# shelves_v05.net
KiCad netlist of a schematic drawn in EAGLE
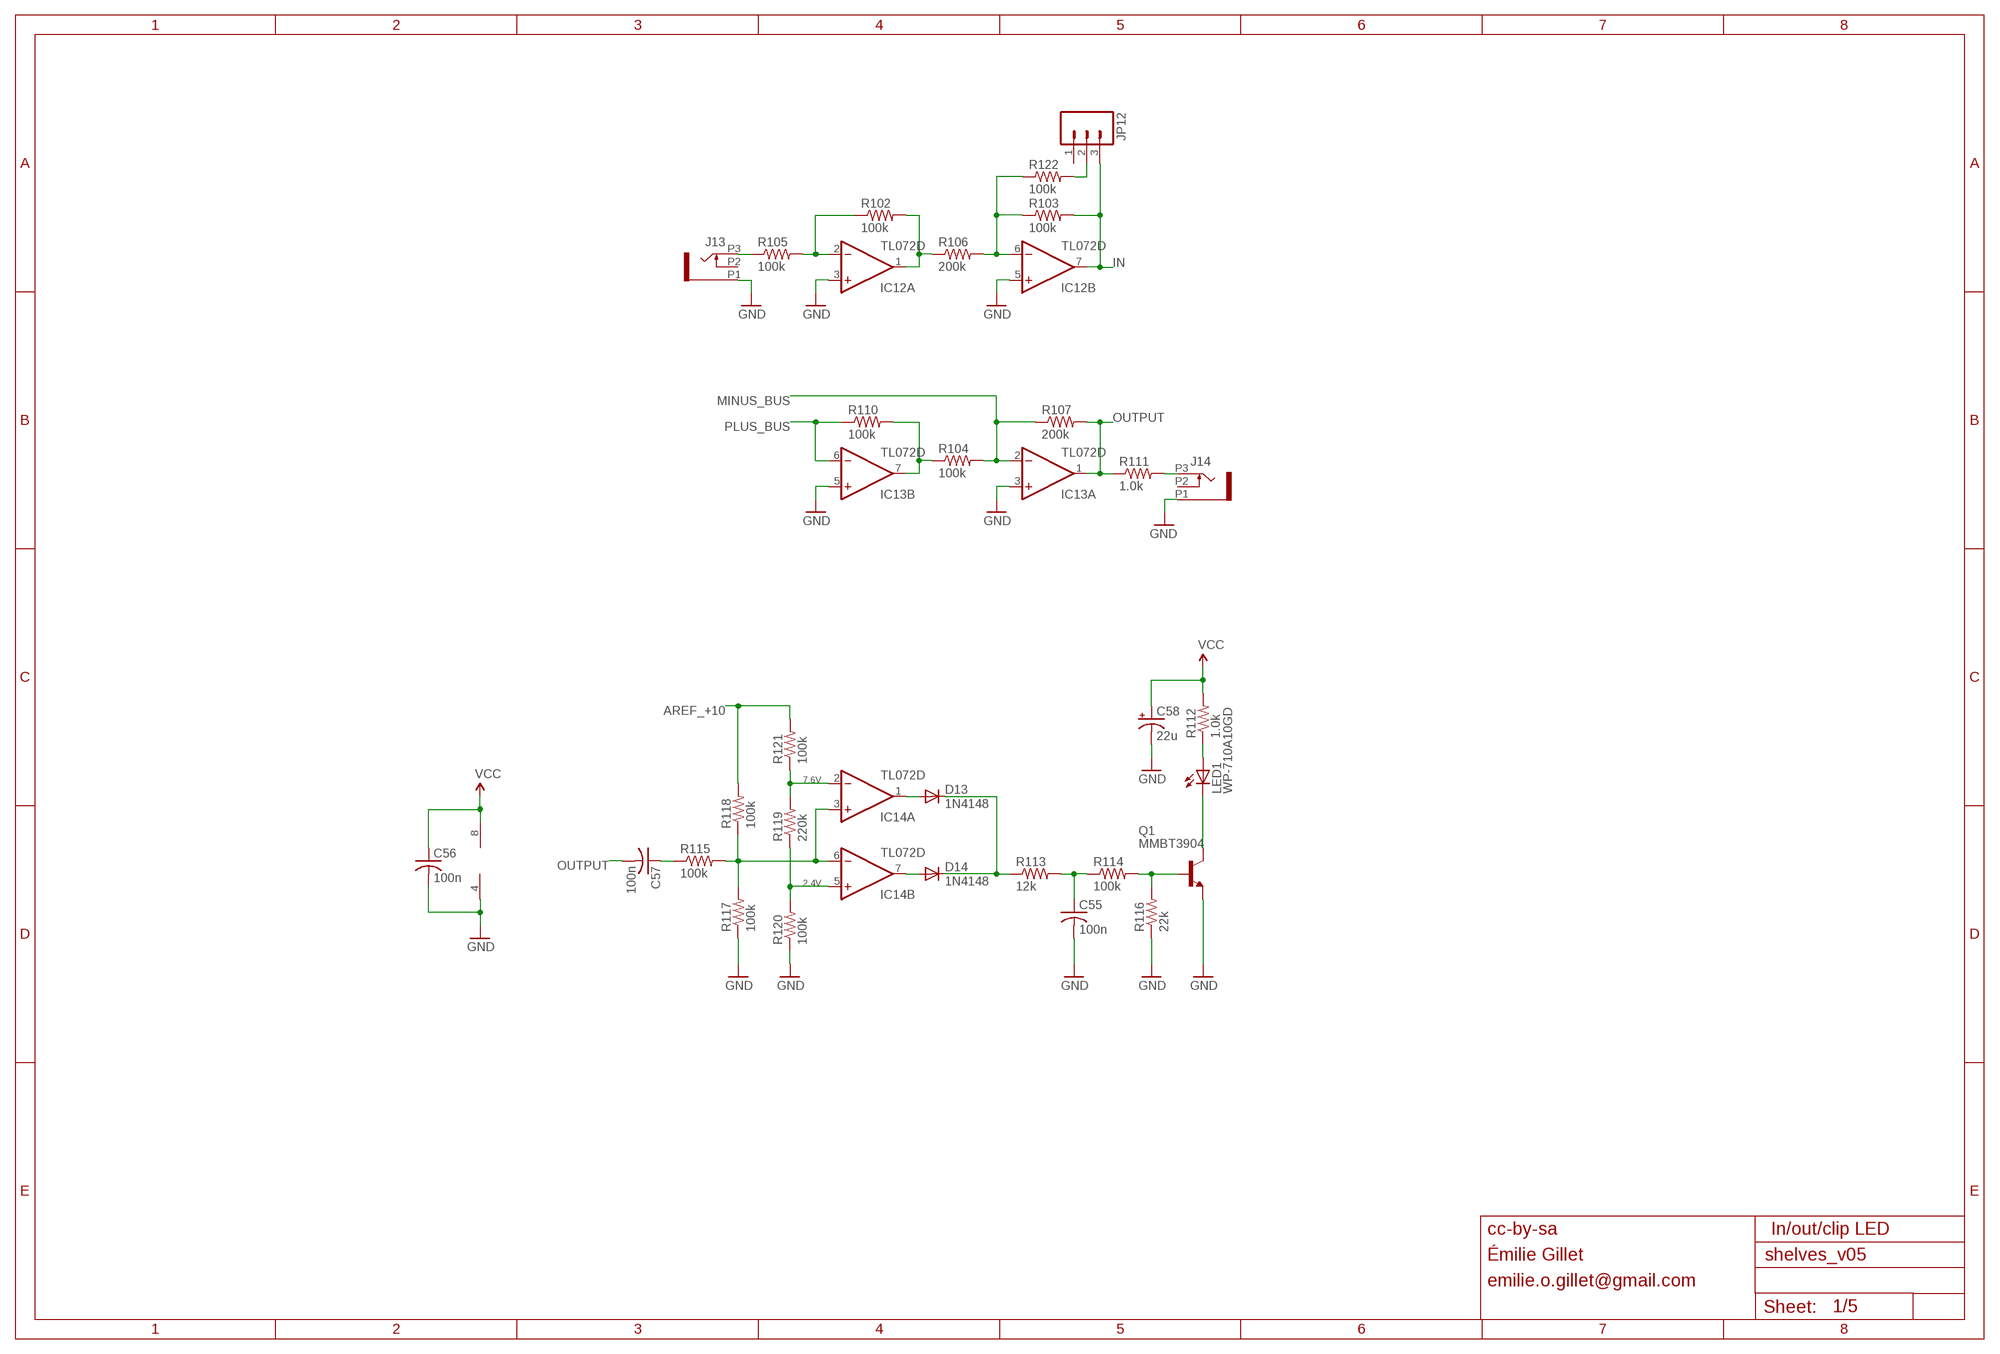
[diagram p0: schematic, sheet 1]
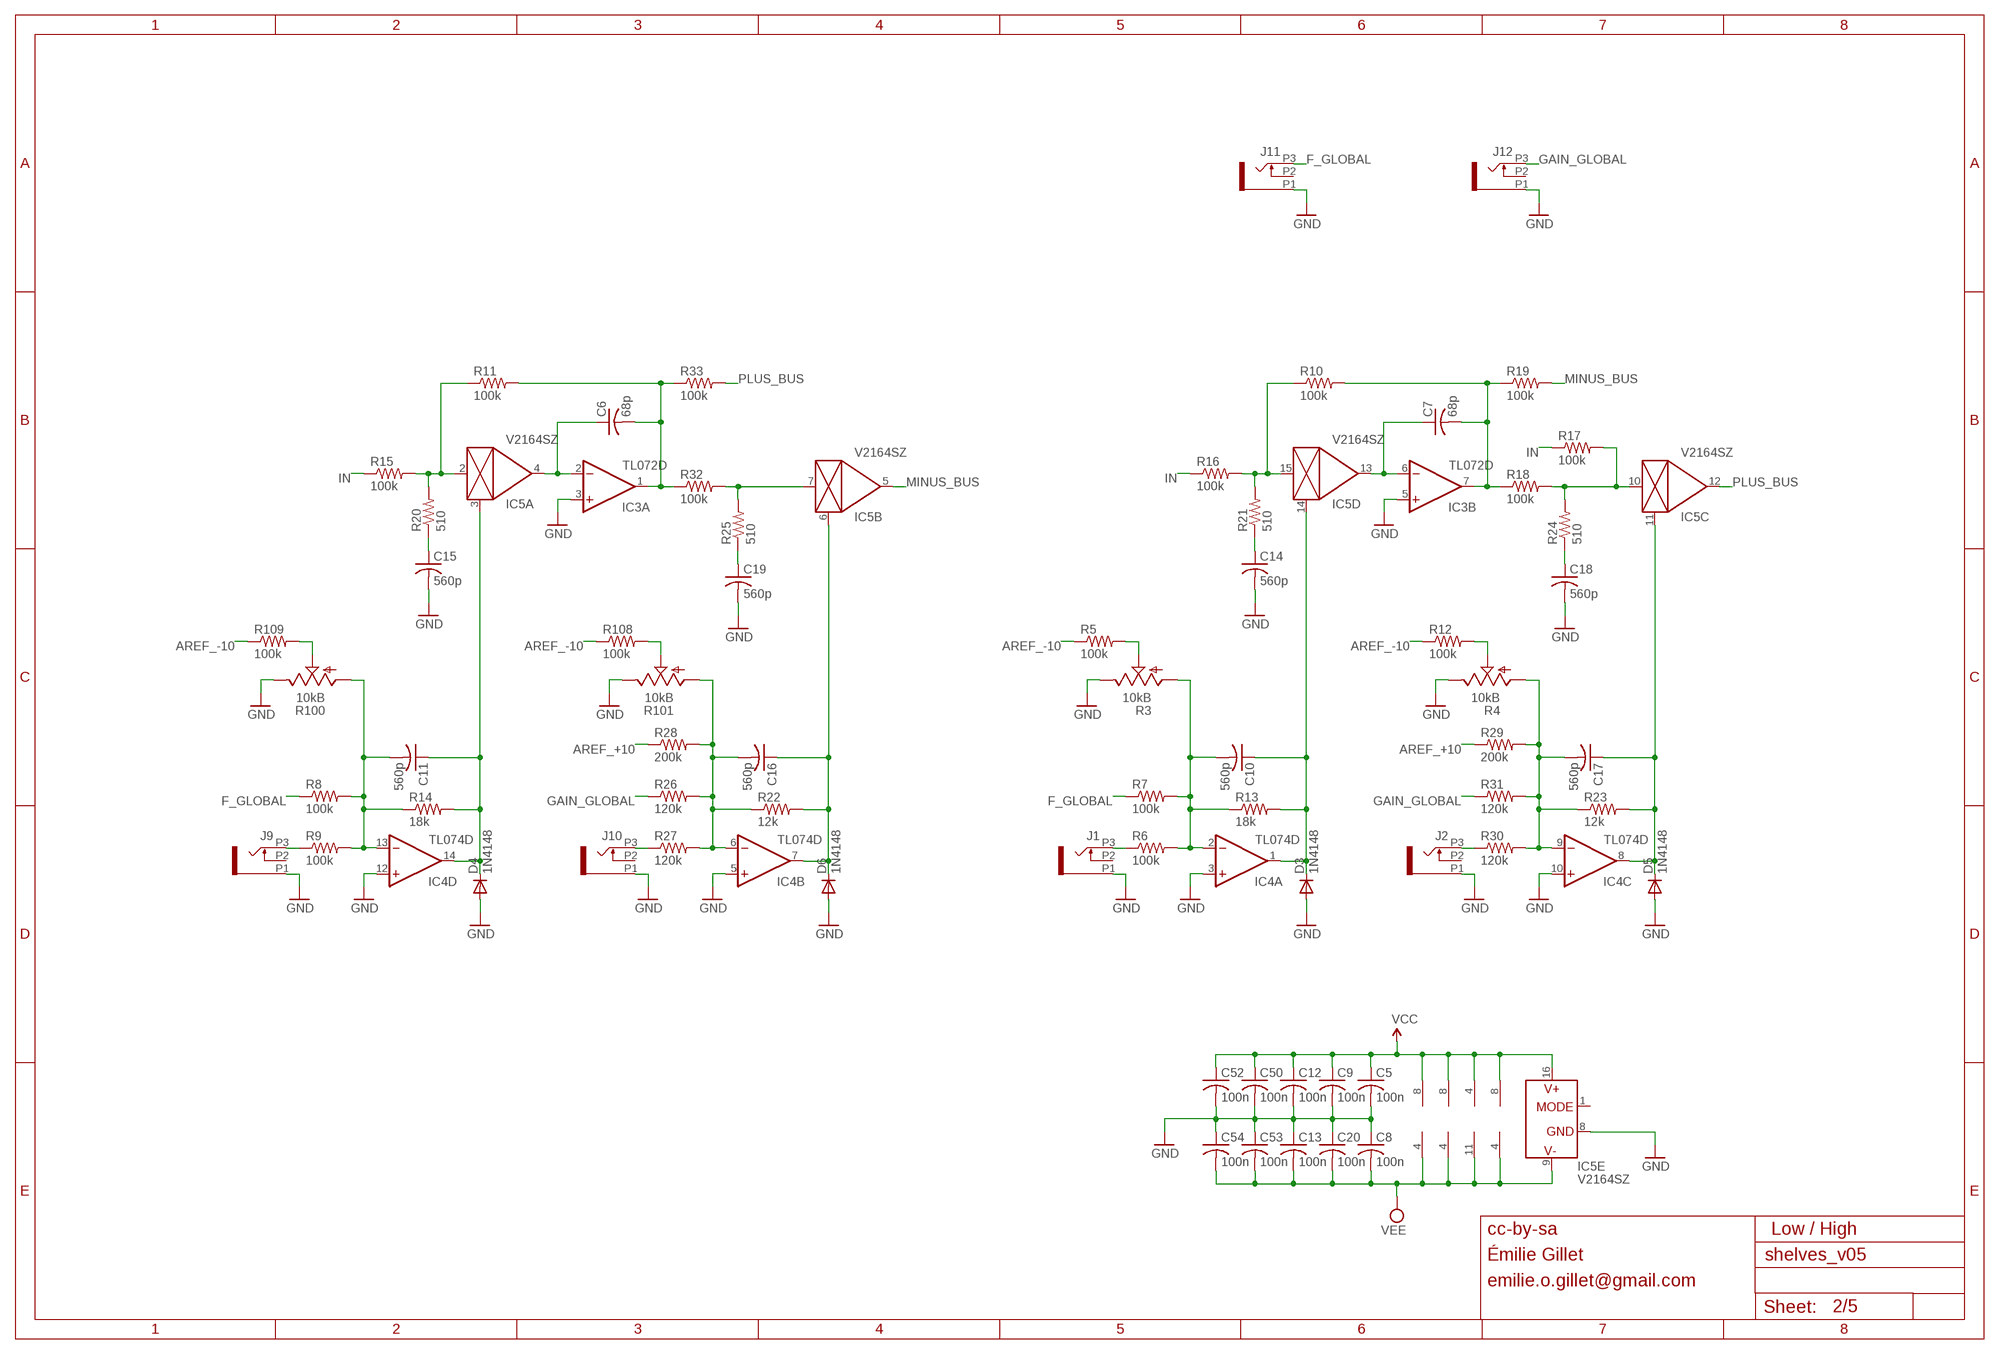
[diagram p1: schematic, sheet 2]
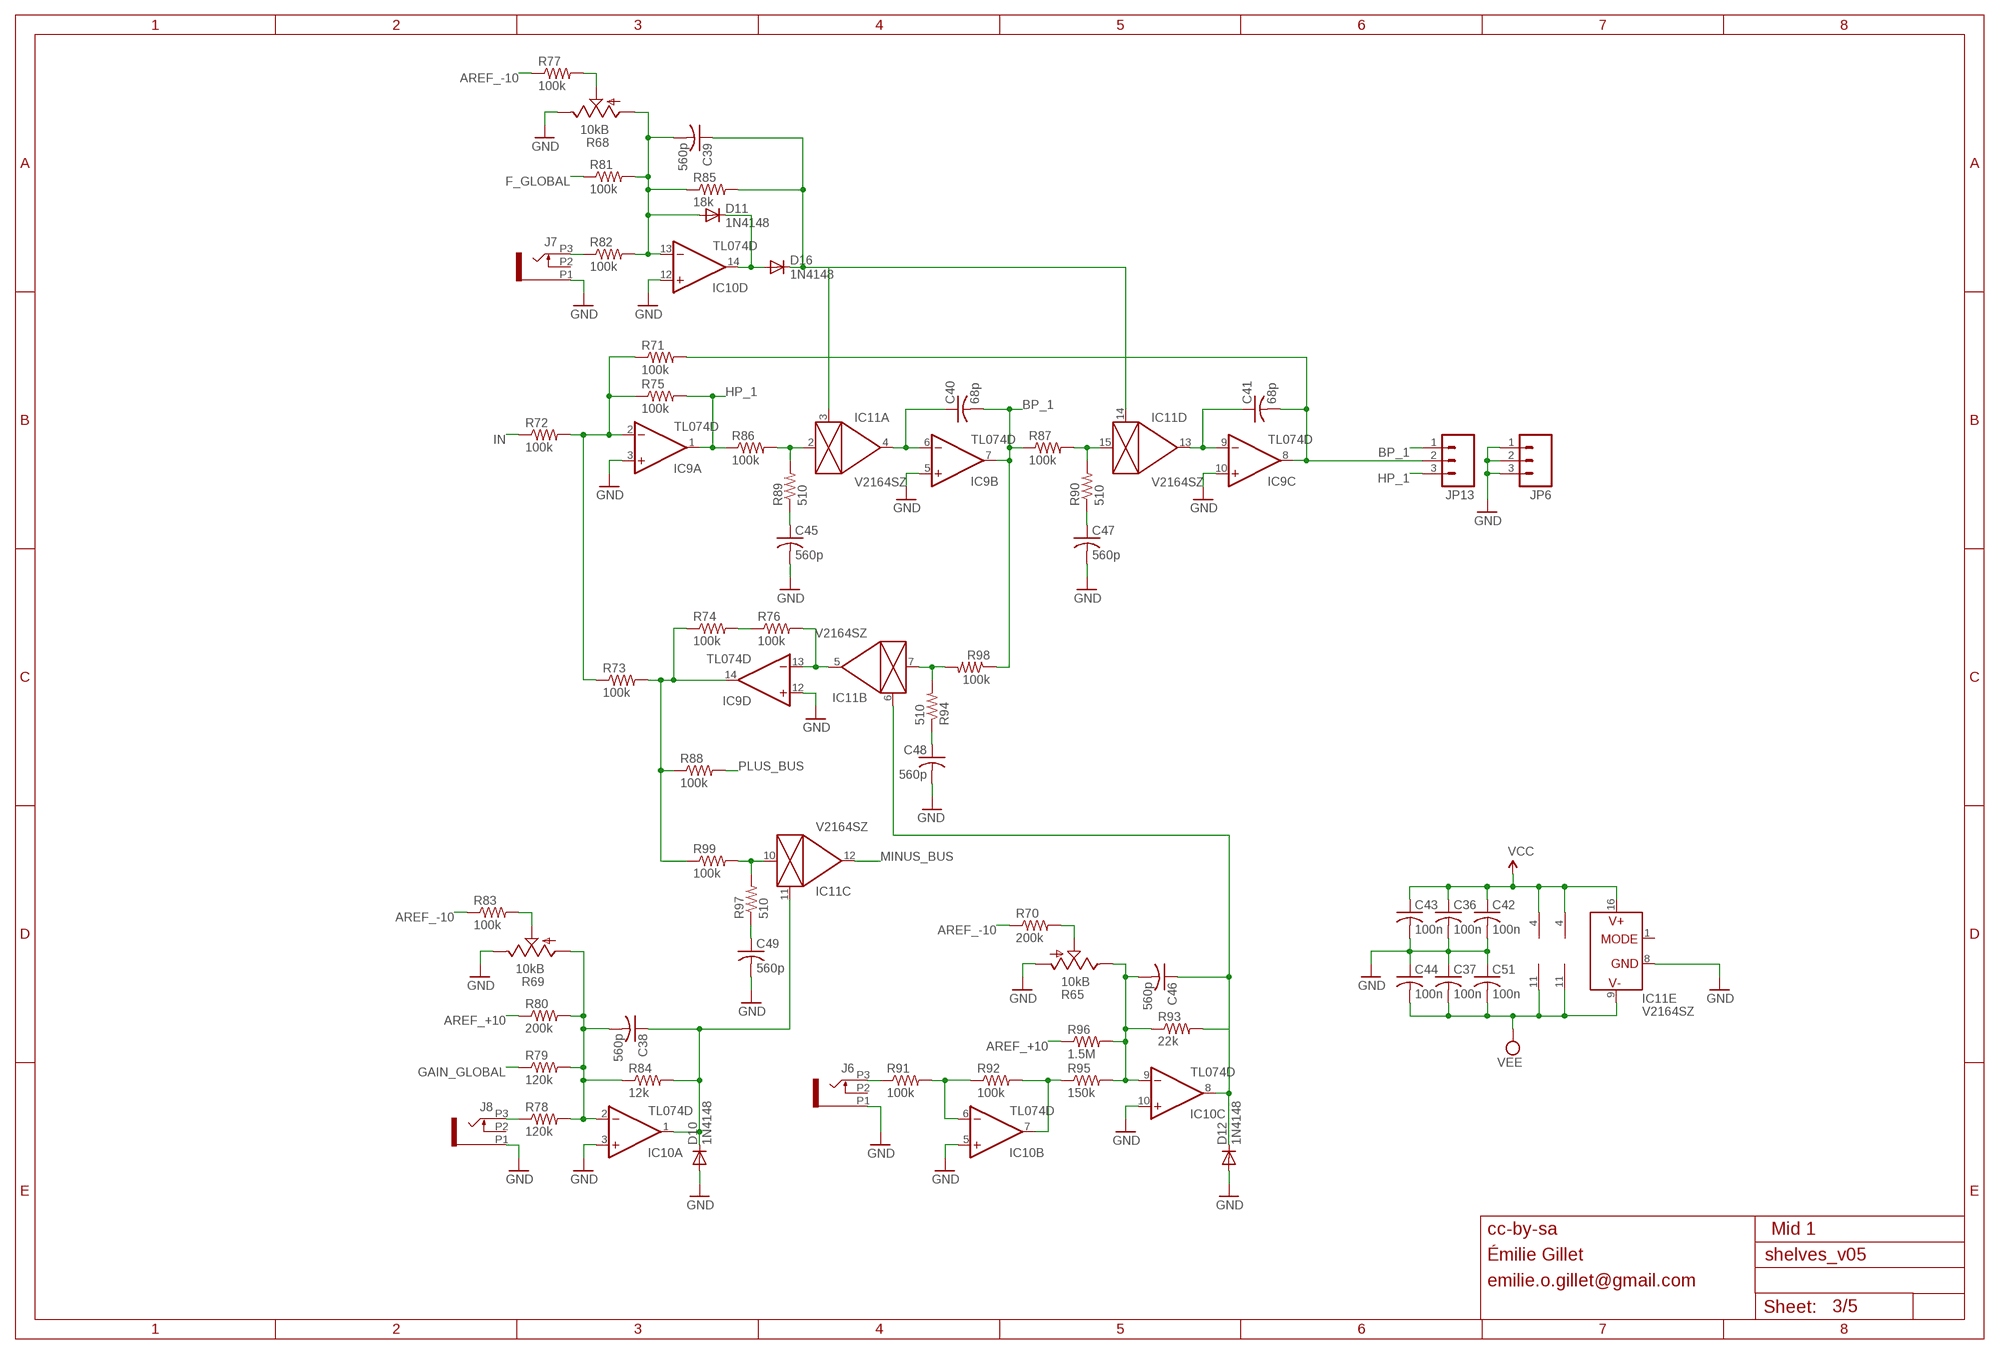
[diagram p2: schematic, sheet 3]
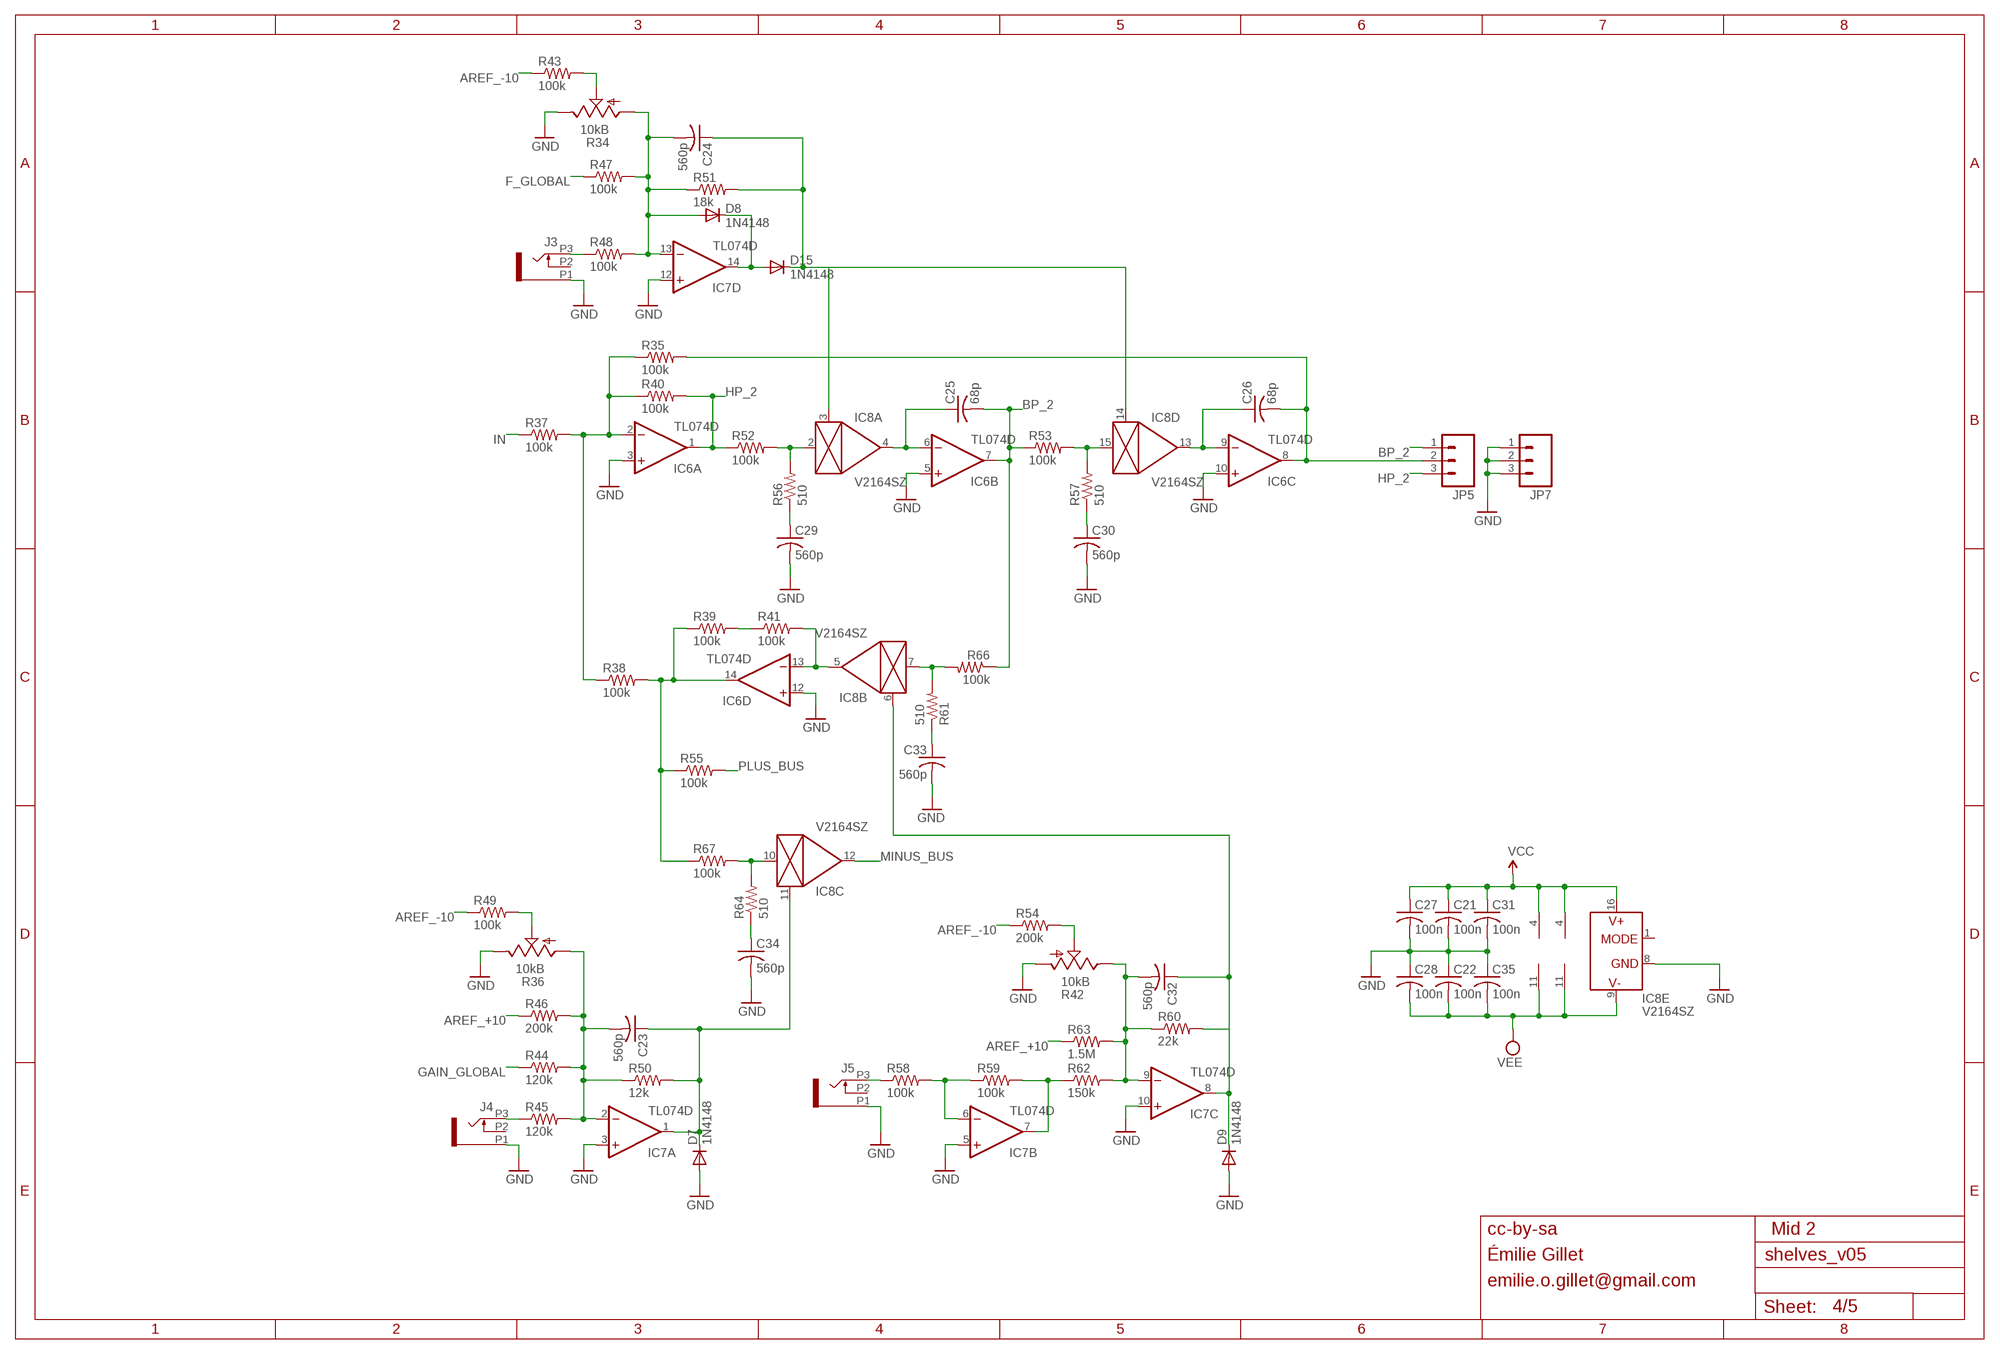
[diagram p3: schematic, sheet 4]
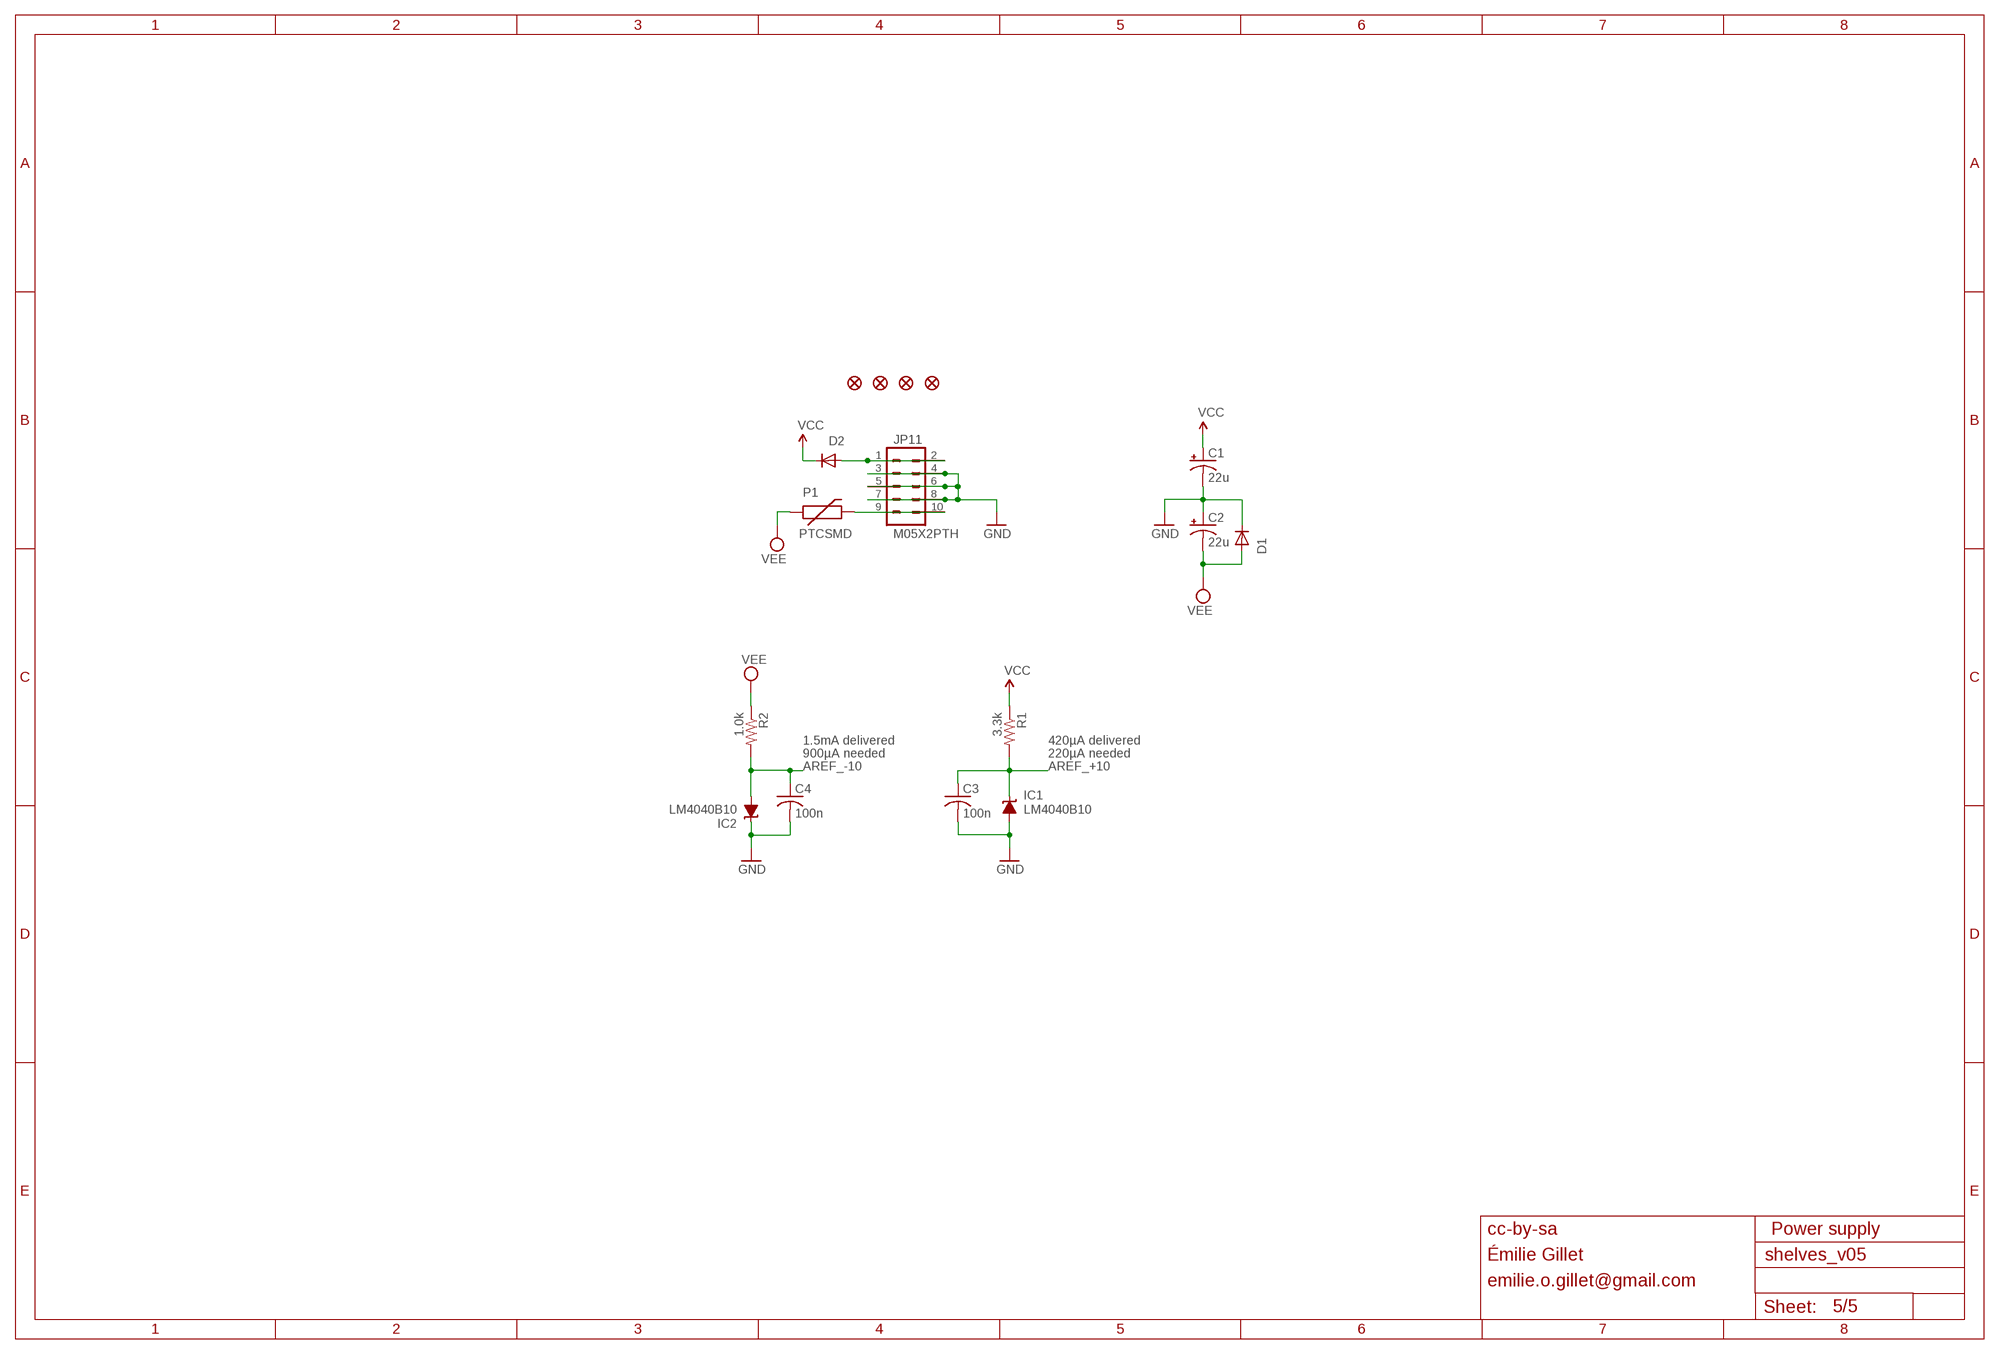
[diagram p4: schematic, sheet 5]

(export (version "E")
  (design (tool "Eeschema 10.0.6"))
  (components
    (comp (ref "C36")
      (value "100n")
      (footprint "eagle-import:C0603")
      (libsource (lib "eagle-import") (part "C-USC0603"))
    )
    (comp (ref "C37")
      (value "100n")
      (footprint "eagle-import:C0603")
      (libsource (lib "eagle-import") (part "C-USC0603"))
    )
    (comp (ref "C38")
      (value "560p")
      (footprint "eagle-import:C0603")
      (libsource (lib "eagle-import") (part "C-USC0603"))
    )
    (comp (ref "C39")
      (value "560p")
      (footprint "eagle-import:C0603")
      (libsource (lib "eagle-import") (part "C-USC0603"))
    )
    (comp (ref "C40")
      (value "68p")
      (footprint "eagle-import:C0603")
      (libsource (lib "eagle-import") (part "C-USC0603"))
    )
    (comp (ref "C41")
      (value "68p")
      (footprint "eagle-import:C0603")
      (libsource (lib "eagle-import") (part "C-USC0603"))
    )
    (comp (ref "C42")
      (value "100n")
      (footprint "eagle-import:C0603")
      (libsource (lib "eagle-import") (part "C-USC0603"))
    )
    (comp (ref "C43")
      (value "100n")
      (footprint "eagle-import:C0603")
      (libsource (lib "eagle-import") (part "C-USC0603"))
    )
    (comp (ref "C44")
      (value "100n")
      (footprint "eagle-import:C0603")
      (libsource (lib "eagle-import") (part "C-USC0603"))
    )
    (comp (ref "C45")
      (value "560p")
      (footprint "eagle-import:C0603")
      (libsource (lib "eagle-import") (part "C-USC0603"))
    )
    (comp (ref "C46")
      (value "560p")
      (footprint "eagle-import:C0603")
      (libsource (lib "eagle-import") (part "C-USC0603"))
    )
    (comp (ref "C47")
      (value "560p")
      (footprint "eagle-import:C0603")
      (libsource (lib "eagle-import") (part "C-USC0603"))
    )
    (comp (ref "C48")
      (value "560p")
      (footprint "eagle-import:C0603")
      (libsource (lib "eagle-import") (part "C-USC0603"))
    )
    (comp (ref "C49")
      (value "560p")
      (footprint "eagle-import:C0603")
      (libsource (lib "eagle-import") (part "C-USC0603"))
    )
    (comp (ref "C51")
      (value "100n")
      (footprint "eagle-import:C0603")
      (libsource (lib "eagle-import") (part "C-USC0603"))
    )
    (comp (ref "D10")
      (value "1N4148")
      (footprint "eagle-import:SOD323-W")
      (libsource (lib "eagle-import") (part "DIODE-SOD323-W"))
    )
    (comp (ref "D11")
      (value "1N4148")
      (footprint "eagle-import:SOD323-W")
      (libsource (lib "eagle-import") (part "DIODE-SOD323-W"))
    )
    (comp (ref "D12")
      (value "1N4148")
      (footprint "eagle-import:SOD323-W")
      (libsource (lib "eagle-import") (part "DIODE-SOD323-W"))
    )
    (comp (ref "D16")
      (value "1N4148")
      (footprint "eagle-import:SOD323-W")
      (libsource (lib "eagle-import") (part "DIODE-SOD323-W"))
    )
    (comp (ref "IC9")
      (value "TL074D")
      (footprint "eagle-import:SO14")
      (libsource (lib "eagle-import") (part "TL074D"))
    )
    (comp (ref "IC10")
      (value "TL074D")
      (footprint "eagle-import:SO14")
      (libsource (lib "eagle-import") (part "TL074D"))
    )
    (comp (ref "IC11")
      (value "V2164SZ")
      (footprint "eagle-import:SOIC16N")
      (libsource (lib "eagle-import") (part "SSM2164S"))
    )
    (comp (ref "J6")
      (value "PJ301_THONKICONN6")
      (footprint "eagle-import:WQP_PJ_301M6")
      (libsource (lib "eagle-import") (part "PJ301_THONKICONN6"))
    )
    (comp (ref "J7")
      (value "PJ301_THONKICONN6")
      (footprint "eagle-import:WQP_PJ_301M6")
      (libsource (lib "eagle-import") (part "PJ301_THONKICONN6"))
    )
    (comp (ref "J8")
      (value "PJ301_THONKICONN6")
      (footprint "eagle-import:WQP_PJ_301M6")
      (libsource (lib "eagle-import") (part "PJ301_THONKICONN6"))
    )
    (comp (ref "JP6")
      (value "M03PTH")
      (footprint "eagle-import:1X03")
      (libsource (lib "eagle-import") (part "M03PTH"))
    )
    (comp (ref "JP13")
      (value "M03PTH")
      (footprint "eagle-import:1X03")
      (libsource (lib "eagle-import") (part "M03PTH"))
    )
    (comp (ref "R65")
      (value "10kB")
      (footprint "eagle-import:ALPS_POT_VERTICAL")
      (libsource (lib "eagle-import") (part "POT_USVERTICAL"))
    )
    (comp (ref "R68")
      (value "10kB")
      (footprint "eagle-import:ALPS_POT_VERTICAL_PS")
      (libsource (lib "eagle-import") (part "POT_USVERTICAL_PS"))
    )
    (comp (ref "R69")
      (value "10kB")
      (footprint "eagle-import:ALPS_POT_VERTICAL_PS")
      (libsource (lib "eagle-import") (part "POT_USVERTICAL_PS"))
    )
    (comp (ref "R70")
      (value "200k")
      (footprint "eagle-import:R0603")
      (libsource (lib "eagle-import") (part "R-US_R0603"))
    )
    (comp (ref "R71")
      (value "100k")
      (footprint "eagle-import:R0603")
      (libsource (lib "eagle-import") (part "R-US_R0603"))
    )
    (comp (ref "R72")
      (value "100k")
      (footprint "eagle-import:R0603")
      (libsource (lib "eagle-import") (part "R-US_R0603"))
    )
    (comp (ref "R73")
      (value "100k")
      (footprint "eagle-import:R0603")
      (libsource (lib "eagle-import") (part "R-US_R0603"))
    )
    (comp (ref "R74")
      (value "100k")
      (footprint "eagle-import:R0603")
      (libsource (lib "eagle-import") (part "R-US_R0603"))
    )
    (comp (ref "R75")
      (value "100k")
      (footprint "eagle-import:R0603")
      (libsource (lib "eagle-import") (part "R-US_R0603"))
    )
    (comp (ref "R76")
      (value "100k")
      (footprint "eagle-import:R0603")
      (libsource (lib "eagle-import") (part "R-US_R0603"))
    )
    (comp (ref "R77")
      (value "100k")
      (footprint "eagle-import:R0603")
      (libsource (lib "eagle-import") (part "R-US_R0603"))
    )
    (comp (ref "R78")
      (value "120k")
      (footprint "eagle-import:R0603")
      (libsource (lib "eagle-import") (part "R-US_R0603"))
    )
    (comp (ref "R79")
      (value "120k")
      (footprint "eagle-import:R0603")
      (libsource (lib "eagle-import") (part "R-US_R0603"))
    )
    (comp (ref "R80")
      (value "200k")
      (footprint "eagle-import:R0603")
      (libsource (lib "eagle-import") (part "R-US_R0603"))
    )
    (comp (ref "R81")
      (value "100k")
      (footprint "eagle-import:R0603")
      (libsource (lib "eagle-import") (part "R-US_R0603"))
    )
    (comp (ref "R82")
      (value "100k")
      (footprint "eagle-import:R0603")
      (libsource (lib "eagle-import") (part "R-US_R0603"))
    )
    (comp (ref "R83")
      (value "100k")
      (footprint "eagle-import:R0603")
      (libsource (lib "eagle-import") (part "R-US_R0603"))
    )
    (comp (ref "R84")
      (value "12k")
      (footprint "eagle-import:R0603")
      (libsource (lib "eagle-import") (part "R-US_R0603"))
    )
    (comp (ref "R85")
      (value "18k")
      (footprint "eagle-import:R0603")
      (libsource (lib "eagle-import") (part "R-US_R0603"))
    )
    (comp (ref "R86")
      (value "100k")
      (footprint "eagle-import:R0603")
      (libsource (lib "eagle-import") (part "R-US_R0603"))
    )
    (comp (ref "R87")
      (value "100k")
      (footprint "eagle-import:R0603")
      (libsource (lib "eagle-import") (part "R-US_R0603"))
    )
    (comp (ref "R88")
      (value "100k")
      (footprint "eagle-import:R0603")
      (libsource (lib "eagle-import") (part "R-US_R0603"))
    )
    (comp (ref "R89")
      (value "510")
      (footprint "eagle-import:R0603")
      (libsource (lib "eagle-import") (part "R-US_R0603"))
    )
    (comp (ref "R90")
      (value "510")
      (footprint "eagle-import:R0603")
      (libsource (lib "eagle-import") (part "R-US_R0603"))
    )
    (comp (ref "R91")
      (value "100k")
      (footprint "eagle-import:R0603")
      (libsource (lib "eagle-import") (part "R-US_R0603"))
    )
    (comp (ref "R92")
      (value "100k")
      (footprint "eagle-import:R0603")
      (libsource (lib "eagle-import") (part "R-US_R0603"))
    )
    (comp (ref "R93")
      (value "22k")
      (footprint "eagle-import:R0603")
      (libsource (lib "eagle-import") (part "R-US_R0603"))
    )
    (comp (ref "R94")
      (value "510")
      (footprint "eagle-import:R0603")
      (libsource (lib "eagle-import") (part "R-US_R0603"))
    )
    (comp (ref "R95")
      (value "150k")
      (footprint "eagle-import:R0603")
      (libsource (lib "eagle-import") (part "R-US_R0603"))
    )
    (comp (ref "R96")
      (value "1.5M")
      (footprint "eagle-import:R0603")
      (libsource (lib "eagle-import") (part "R-US_R0603"))
    )
    (comp (ref "R97")
      (value "510")
      (footprint "eagle-import:R0603")
      (libsource (lib "eagle-import") (part "R-US_R0603"))
    )
    (comp (ref "R98")
      (value "100k")
      (footprint "eagle-import:R0603")
      (libsource (lib "eagle-import") (part "R-US_R0603"))
    )
    (comp (ref "R99")
      (value "100k")
      (footprint "eagle-import:R0603")
      (libsource (lib "eagle-import") (part "R-US_R0603"))
    )
    (comp (ref "C1")
      (value "22u")
      (footprint "eagle-import:PANASONIC_C")
      (libsource (lib "eagle-import") (part "CPOL-USC"))
    )
    (comp (ref "C2")
      (value "22u")
      (footprint "eagle-import:PANASONIC_C")
      (libsource (lib "eagle-import") (part "CPOL-USC"))
    )
    (comp (ref "C3")
      (value "100n")
      (footprint "eagle-import:C0603")
      (libsource (lib "eagle-import") (part "C-USC0603"))
    )
    (comp (ref "C4")
      (value "100n")
      (footprint "eagle-import:C0603")
      (libsource (lib "eagle-import") (part "C-USC0603"))
    )
    (comp (ref "D1")
      (value "1N5819HW")
      (footprint "eagle-import:SOD123")
      (libsource (lib "eagle-import") (part "DIODE-SOD123"))
    )
    (comp (ref "D2")
      (value "1N5819HW")
      (footprint "eagle-import:SOD123")
      (libsource (lib "eagle-import") (part "DIODE-SOD123"))
    )
    (comp (ref "IC1")
      (value "LM4040B10")
      (footprint "eagle-import:DBZ_R-PDSO-G3")
      (libsource (lib "eagle-import") (part "LM4041DBZB12"))
    )
    (comp (ref "IC2")
      (value "LM4040B10")
      (footprint "eagle-import:DBZ_R-PDSO-G3")
      (libsource (lib "eagle-import") (part "LM4041DBZB12"))
    )
    (comp (ref "JP1")
      (value "FIDUCIAL1X2")
      (footprint "eagle-import:FIDUCIAL-1X2")
      (libsource (lib "eagle-import") (part "FIDUCIAL1X2"))
    )
    (comp (ref "JP2")
      (value "FIDUCIAL1X2")
      (footprint "eagle-import:FIDUCIAL-1X2")
      (libsource (lib "eagle-import") (part "FIDUCIAL1X2"))
    )
    (comp (ref "JP3")
      (value "FIDUCIAL1X2")
      (footprint "eagle-import:FIDUCIAL-1X2")
      (libsource (lib "eagle-import") (part "FIDUCIAL1X2"))
    )
    (comp (ref "JP4")
      (value "FIDUCIAL1X2")
      (footprint "eagle-import:FIDUCIAL-1X2")
      (libsource (lib "eagle-import") (part "FIDUCIAL1X2"))
    )
    (comp (ref "JP11")
      (value "M05X2PTH")
      (footprint "eagle-import:AVR_ICSP")
      (libsource (lib "eagle-import") (part "M05X2PTH"))
    )
    (comp (ref "P1")
      (value "PTCSMD")
      (footprint "eagle-import:PTC-1206")
      (libsource (lib "eagle-import") (part "PTCSMD"))
    )
    (comp (ref "R1")
      (value "3.3k")
      (footprint "eagle-import:R0603")
      (libsource (lib "eagle-import") (part "R-US_R0603"))
    )
    (comp (ref "R2")
      (value "1.0k")
      (footprint "eagle-import:R0603")
      (libsource (lib "eagle-import") (part "R-US_R0603"))
    )
    (comp (ref "C5")
      (value "100n")
      (footprint "eagle-import:C0603")
      (libsource (lib "eagle-import") (part "C-USC0603"))
    )
    (comp (ref "C6")
      (value "68p")
      (footprint "eagle-import:C0603")
      (libsource (lib "eagle-import") (part "C-USC0603"))
    )
    (comp (ref "C7")
      (value "68p")
      (footprint "eagle-import:C0603")
      (libsource (lib "eagle-import") (part "C-USC0603"))
    )
    (comp (ref "C8")
      (value "100n")
      (footprint "eagle-import:C0603")
      (libsource (lib "eagle-import") (part "C-USC0603"))
    )
    (comp (ref "C9")
      (value "100n")
      (footprint "eagle-import:C0603")
      (libsource (lib "eagle-import") (part "C-USC0603"))
    )
    (comp (ref "C10")
      (value "560p")
      (footprint "eagle-import:C0603")
      (libsource (lib "eagle-import") (part "C-USC0603"))
    )
    (comp (ref "C11")
      (value "560p")
      (footprint "eagle-import:C0603")
      (libsource (lib "eagle-import") (part "C-USC0603"))
    )
    (comp (ref "C12")
      (value "100n")
      (footprint "eagle-import:C0603")
      (libsource (lib "eagle-import") (part "C-USC0603"))
    )
    (comp (ref "C13")
      (value "100n")
      (footprint "eagle-import:C0603")
      (libsource (lib "eagle-import") (part "C-USC0603"))
    )
    (comp (ref "C14")
      (value "560p")
      (footprint "eagle-import:C0603")
      (libsource (lib "eagle-import") (part "C-USC0603"))
    )
    (comp (ref "C15")
      (value "560p")
      (footprint "eagle-import:C0603")
      (libsource (lib "eagle-import") (part "C-USC0603"))
    )
    (comp (ref "C16")
      (value "560p")
      (footprint "eagle-import:C0603")
      (libsource (lib "eagle-import") (part "C-USC0603"))
    )
    (comp (ref "C17")
      (value "560p")
      (footprint "eagle-import:C0603")
      (libsource (lib "eagle-import") (part "C-USC0603"))
    )
    (comp (ref "C18")
      (value "560p")
      (footprint "eagle-import:C0603")
      (libsource (lib "eagle-import") (part "C-USC0603"))
    )
    (comp (ref "C19")
      (value "560p")
      (footprint "eagle-import:C0603")
      (libsource (lib "eagle-import") (part "C-USC0603"))
    )
    (comp (ref "C20")
      (value "100n")
      (footprint "eagle-import:C0603")
      (libsource (lib "eagle-import") (part "C-USC0603"))
    )
    (comp (ref "C50")
      (value "100n")
      (footprint "eagle-import:C0603")
      (libsource (lib "eagle-import") (part "C-USC0603"))
    )
    (comp (ref "C52")
      (value "100n")
      (footprint "eagle-import:C0603")
      (libsource (lib "eagle-import") (part "C-USC0603"))
    )
    (comp (ref "C53")
      (value "100n")
      (footprint "eagle-import:C0603")
      (libsource (lib "eagle-import") (part "C-USC0603"))
    )
    (comp (ref "C54")
      (value "100n")
      (footprint "eagle-import:C0603")
      (libsource (lib "eagle-import") (part "C-USC0603"))
    )
    (comp (ref "D3")
      (value "1N4148")
      (footprint "eagle-import:SOD323-W")
      (libsource (lib "eagle-import") (part "DIODE-SOD323-W"))
    )
    (comp (ref "D4")
      (value "1N4148")
      (footprint "eagle-import:SOD323-W")
      (libsource (lib "eagle-import") (part "DIODE-SOD323-W"))
    )
    (comp (ref "D5")
      (value "1N4148")
      (footprint "eagle-import:SOD323-W")
      (libsource (lib "eagle-import") (part "DIODE-SOD323-W"))
    )
    (comp (ref "D6")
      (value "1N4148")
      (footprint "eagle-import:SOD323-W")
      (libsource (lib "eagle-import") (part "DIODE-SOD323-W"))
    )
    (comp (ref "IC3")
      (value "TL072D")
      (footprint "eagle-import:SO08")
      (libsource (lib "eagle-import") (part "TL072D"))
    )
    (comp (ref "IC4")
      (value "TL074D")
      (footprint "eagle-import:SO14")
      (libsource (lib "eagle-import") (part "TL074D"))
    )
    (comp (ref "IC5")
      (value "V2164SZ")
      (footprint "eagle-import:SOIC16N")
      (libsource (lib "eagle-import") (part "SSM2164S"))
    )
    (comp (ref "IC12")
      (value "TL072D")
      (footprint "eagle-import:SO08")
      (libsource (lib "eagle-import") (part "TL072D"))
    )
    (comp (ref "IC13")
      (value "TL072D")
      (footprint "eagle-import:SO08")
      (libsource (lib "eagle-import") (part "TL072D"))
    )
    (comp (ref "J1")
      (value "PJ301_THONKICONN6")
      (footprint "eagle-import:WQP_PJ_301M6")
      (libsource (lib "eagle-import") (part "PJ301_THONKICONN6"))
    )
    (comp (ref "J2")
      (value "PJ301_THONKICONN6")
      (footprint "eagle-import:WQP_PJ_301M6")
      (libsource (lib "eagle-import") (part "PJ301_THONKICONN6"))
    )
    (comp (ref "J9")
      (value "PJ301_THONKICONN6")
      (footprint "eagle-import:WQP_PJ_301M6")
      (libsource (lib "eagle-import") (part "PJ301_THONKICONN6"))
    )
    (comp (ref "J10")
      (value "PJ301_THONKICONN6")
      (footprint "eagle-import:WQP_PJ_301M6")
      (libsource (lib "eagle-import") (part "PJ301_THONKICONN6"))
    )
    (comp (ref "J11")
      (value "PJ301_THONKICONN6")
      (footprint "eagle-import:WQP_PJ_301M6")
      (libsource (lib "eagle-import") (part "PJ301_THONKICONN6"))
    )
    (comp (ref "J12")
      (value "PJ301_THONKICONN6")
      (footprint "eagle-import:WQP_PJ_301M6")
      (libsource (lib "eagle-import") (part "PJ301_THONKICONN6"))
    )
    (comp (ref "R3")
      (value "10kB")
      (footprint "eagle-import:ALPS_POT_VERTICAL_PS")
      (libsource (lib "eagle-import") (part "POT_USVERTICAL_PS"))
    )
    (comp (ref "R4")
      (value "10kB")
      (footprint "eagle-import:ALPS_POT_VERTICAL_PS")
      (libsource (lib "eagle-import") (part "POT_USVERTICAL_PS"))
    )
    (comp (ref "R5")
      (value "100k")
      (footprint "eagle-import:R0603")
      (libsource (lib "eagle-import") (part "R-US_R0603"))
    )
    (comp (ref "R6")
      (value "100k")
      (footprint "eagle-import:R0603")
      (libsource (lib "eagle-import") (part "R-US_R0603"))
    )
    (comp (ref "R7")
      (value "100k")
      (footprint "eagle-import:R0603")
      (libsource (lib "eagle-import") (part "R-US_R0603"))
    )
    (comp (ref "R8")
      (value "100k")
      (footprint "eagle-import:R0603")
      (libsource (lib "eagle-import") (part "R-US_R0603"))
    )
    (comp (ref "R9")
      (value "100k")
      (footprint "eagle-import:R0603")
      (libsource (lib "eagle-import") (part "R-US_R0603"))
    )
    (comp (ref "R10")
      (value "100k")
      (footprint "eagle-import:R0603")
      (libsource (lib "eagle-import") (part "R-US_R0603"))
    )
    (comp (ref "R11")
      (value "100k")
      (footprint "eagle-import:R0603")
      (libsource (lib "eagle-import") (part "R-US_R0603"))
    )
    (comp (ref "R12")
      (value "100k")
      (footprint "eagle-import:R0603")
      (libsource (lib "eagle-import") (part "R-US_R0603"))
    )
    (comp (ref "R13")
      (value "18k")
      (footprint "eagle-import:R0603")
      (libsource (lib "eagle-import") (part "R-US_R0603"))
    )
    (comp (ref "R14")
      (value "18k")
      (footprint "eagle-import:R0603")
      (libsource (lib "eagle-import") (part "R-US_R0603"))
    )
    (comp (ref "R15")
      (value "100k")
      (footprint "eagle-import:R0603")
      (libsource (lib "eagle-import") (part "R-US_R0603"))
    )
    (comp (ref "R16")
      (value "100k")
      (footprint "eagle-import:R0603")
      (libsource (lib "eagle-import") (part "R-US_R0603"))
    )
    (comp (ref "R17")
      (value "100k")
      (footprint "eagle-import:R0603")
      (libsource (lib "eagle-import") (part "R-US_R0603"))
    )
    (comp (ref "R18")
      (value "100k")
      (footprint "eagle-import:R0603")
      (libsource (lib "eagle-import") (part "R-US_R0603"))
    )
    (comp (ref "R19")
      (value "100k")
      (footprint "eagle-import:R0603")
      (libsource (lib "eagle-import") (part "R-US_R0603"))
    )
    (comp (ref "R20")
      (value "510")
      (footprint "eagle-import:R0603")
      (libsource (lib "eagle-import") (part "R-US_R0603"))
    )
    (comp (ref "R21")
      (value "510")
      (footprint "eagle-import:R0603")
      (libsource (lib "eagle-import") (part "R-US_R0603"))
    )
    (comp (ref "R22")
      (value "12k")
      (footprint "eagle-import:R0603")
      (libsource (lib "eagle-import") (part "R-US_R0603"))
    )
    (comp (ref "R23")
      (value "12k")
      (footprint "eagle-import:R0603")
      (libsource (lib "eagle-import") (part "R-US_R0603"))
    )
    (comp (ref "R24")
      (value "510")
      (footprint "eagle-import:R0603")
      (libsource (lib "eagle-import") (part "R-US_R0603"))
    )
    (comp (ref "R25")
      (value "510")
      (footprint "eagle-import:R0603")
      (libsource (lib "eagle-import") (part "R-US_R0603"))
    )
    (comp (ref "R26")
      (value "120k")
      (footprint "eagle-import:R0603")
      (libsource (lib "eagle-import") (part "R-US_R0603"))
    )
    (comp (ref "R27")
      (value "120k")
      (footprint "eagle-import:R0603")
      (libsource (lib "eagle-import") (part "R-US_R0603"))
    )
    (comp (ref "R28")
      (value "200k")
      (footprint "eagle-import:R0603")
      (libsource (lib "eagle-import") (part "R-US_R0603"))
    )
    (comp (ref "R29")
      (value "200k")
      (footprint "eagle-import:R0603")
      (libsource (lib "eagle-import") (part "R-US_R0603"))
    )
    (comp (ref "R30")
      (value "120k")
      (footprint "eagle-import:R0603")
      (libsource (lib "eagle-import") (part "R-US_R0603"))
    )
    (comp (ref "R31")
      (value "120k")
      (footprint "eagle-import:R0603")
      (libsource (lib "eagle-import") (part "R-US_R0603"))
    )
    (comp (ref "R32")
      (value "100k")
      (footprint "eagle-import:R0603")
      (libsource (lib "eagle-import") (part "R-US_R0603"))
    )
    (comp (ref "R33")
      (value "100k")
      (footprint "eagle-import:R0603")
      (libsource (lib "eagle-import") (part "R-US_R0603"))
    )
    (comp (ref "R100")
      (value "10kB")
      (footprint "eagle-import:ALPS_POT_VERTICAL_PS")
      (libsource (lib "eagle-import") (part "POT_USVERTICAL_PS"))
    )
    (comp (ref "R101")
      (value "10kB")
      (footprint "eagle-import:ALPS_POT_VERTICAL_PS")
      (libsource (lib "eagle-import") (part "POT_USVERTICAL_PS"))
    )
    (comp (ref "R108")
      (value "100k")
      (footprint "eagle-import:R0603")
      (libsource (lib "eagle-import") (part "R-US_R0603"))
    )
    (comp (ref "R109")
      (value "100k")
      (footprint "eagle-import:R0603")
      (libsource (lib "eagle-import") (part "R-US_R0603"))
    )
    (comp (ref "C55")
      (value "100n")
      (footprint "eagle-import:C0603")
      (libsource (lib "eagle-import") (part "C-USC0603"))
    )
    (comp (ref "C56")
      (value "100n")
      (footprint "eagle-import:C0603")
      (libsource (lib "eagle-import") (part "C-USC0603"))
    )
    (comp (ref "C57")
      (value "100n")
      (footprint "eagle-import:C0603")
      (libsource (lib "eagle-import") (part "C-USC0603"))
    )
    (comp (ref "C58")
      (value "22u")
      (footprint "eagle-import:PANASONIC_C")
      (libsource (lib "eagle-import") (part "CPOL-USC"))
    )
    (comp (ref "D13")
      (value "1N4148")
      (footprint "eagle-import:SOD323-W")
      (libsource (lib "eagle-import") (part "DIODE-SOD323-W"))
    )
    (comp (ref "D14")
      (value "1N4148")
      (footprint "eagle-import:SOD323-W")
      (libsource (lib "eagle-import") (part "DIODE-SOD323-W"))
    )
    (comp (ref "IC14")
      (value "TL072D")
      (footprint "eagle-import:SO08")
      (libsource (lib "eagle-import") (part "TL072D"))
    )
    (comp (ref "J13")
      (value "PJ301_THONKICONN6")
      (footprint "eagle-import:WQP_PJ_301M6")
      (libsource (lib "eagle-import") (part "PJ301_THONKICONN6"))
    )
    (comp (ref "J14")
      (value "PJ301_THONKICONN6")
      (footprint "eagle-import:WQP_PJ_301M6")
      (libsource (lib "eagle-import") (part "PJ301_THONKICONN6"))
    )
    (comp (ref "JP12")
      (value "M03PTH")
      (footprint "eagle-import:1X03")
      (libsource (lib "eagle-import") (part "M03PTH"))
    )
    (comp (ref "LED1")
      (value "WP-710A10GD")
      (footprint "eagle-import:LED3MM")
      (libsource (lib "eagle-import") (part "LED3MM"))
    )
    (comp (ref "Q1")
      (value "MMBT3904")
      (footprint "eagle-import:SOT23-BEC")
      (libsource (lib "eagle-import") (part "-NPN-SOT23-BECMMBT3904LT1"))
    )
    (comp (ref "R102")
      (value "100k")
      (footprint "eagle-import:R0603")
      (libsource (lib "eagle-import") (part "R-US_R0603"))
    )
    (comp (ref "R103")
      (value "100k")
      (footprint "eagle-import:R0603")
      (libsource (lib "eagle-import") (part "R-US_R0603"))
    )
    (comp (ref "R104")
      (value "100k")
      (footprint "eagle-import:R0603")
      (libsource (lib "eagle-import") (part "R-US_R0603"))
    )
    (comp (ref "R105")
      (value "100k")
      (footprint "eagle-import:R0603")
      (libsource (lib "eagle-import") (part "R-US_R0603"))
    )
    (comp (ref "R106")
      (value "200k")
      (footprint "eagle-import:R0603")
      (libsource (lib "eagle-import") (part "R-US_R0603"))
    )
    (comp (ref "R107")
      (value "200k")
      (footprint "eagle-import:R0603")
      (libsource (lib "eagle-import") (part "R-US_R0603"))
    )
    (comp (ref "R110")
      (value "100k")
      (footprint "eagle-import:R0603")
      (libsource (lib "eagle-import") (part "R-US_R0603"))
    )
    (comp (ref "R111")
      (value "1.0k")
      (footprint "eagle-import:R0603")
      (libsource (lib "eagle-import") (part "R-US_R0603"))
    )
    (comp (ref "R112")
      (value "1.0k")
      (footprint "eagle-import:R0603")
      (libsource (lib "eagle-import") (part "R-US_R0603"))
    )
    (comp (ref "R113")
      (value "12k")
      (footprint "eagle-import:R0603")
      (libsource (lib "eagle-import") (part "R-US_R0603"))
    )
    (comp (ref "R114")
      (value "100k")
      (footprint "eagle-import:R0603")
      (libsource (lib "eagle-import") (part "R-US_R0603"))
    )
    (comp (ref "R115")
      (value "100k")
      (footprint "eagle-import:R0603")
      (libsource (lib "eagle-import") (part "R-US_R0603"))
    )
    (comp (ref "R116")
      (value "22k")
      (footprint "eagle-import:R0603")
      (libsource (lib "eagle-import") (part "R-US_R0603"))
    )
    (comp (ref "R117")
      (value "100k")
      (footprint "eagle-import:R0603")
      (libsource (lib "eagle-import") (part "R-US_R0603"))
    )
    (comp (ref "R118")
      (value "100k")
      (footprint "eagle-import:R0603")
      (libsource (lib "eagle-import") (part "R-US_R0603"))
    )
    (comp (ref "R119")
      (value "220k")
      (footprint "eagle-import:R0603")
      (libsource (lib "eagle-import") (part "R-US_R0603"))
    )
    (comp (ref "R120")
      (value "100k")
      (footprint "eagle-import:R0603")
      (libsource (lib "eagle-import") (part "R-US_R0603"))
    )
    (comp (ref "R121")
      (value "100k")
      (footprint "eagle-import:R0603")
      (libsource (lib "eagle-import") (part "R-US_R0603"))
    )
    (comp (ref "R122")
      (value "100k")
      (footprint "eagle-import:R0603")
      (libsource (lib "eagle-import") (part "R-US_R0603"))
    )
    (comp (ref "C21")
      (value "100n")
      (footprint "eagle-import:C0603")
      (libsource (lib "eagle-import") (part "C-USC0603"))
    )
    (comp (ref "C22")
      (value "100n")
      (footprint "eagle-import:C0603")
      (libsource (lib "eagle-import") (part "C-USC0603"))
    )
    (comp (ref "C23")
      (value "560p")
      (footprint "eagle-import:C0603")
      (libsource (lib "eagle-import") (part "C-USC0603"))
    )
    (comp (ref "C24")
      (value "560p")
      (footprint "eagle-import:C0603")
      (libsource (lib "eagle-import") (part "C-USC0603"))
    )
    (comp (ref "C25")
      (value "68p")
      (footprint "eagle-import:C0603")
      (libsource (lib "eagle-import") (part "C-USC0603"))
    )
    (comp (ref "C26")
      (value "68p")
      (footprint "eagle-import:C0603")
      (libsource (lib "eagle-import") (part "C-USC0603"))
    )
    (comp (ref "C27")
      (value "100n")
      (footprint "eagle-import:C0603")
      (libsource (lib "eagle-import") (part "C-USC0603"))
    )
    (comp (ref "C28")
      (value "100n")
      (footprint "eagle-import:C0603")
      (libsource (lib "eagle-import") (part "C-USC0603"))
    )
    (comp (ref "C29")
      (value "560p")
      (footprint "eagle-import:C0603")
      (libsource (lib "eagle-import") (part "C-USC0603"))
    )
    (comp (ref "C30")
      (value "560p")
      (footprint "eagle-import:C0603")
      (libsource (lib "eagle-import") (part "C-USC0603"))
    )
    (comp (ref "C31")
      (value "100n")
      (footprint "eagle-import:C0603")
      (libsource (lib "eagle-import") (part "C-USC0603"))
    )
    (comp (ref "C32")
      (value "560p")
      (footprint "eagle-import:C0603")
      (libsource (lib "eagle-import") (part "C-USC0603"))
    )
    (comp (ref "C33")
      (value "560p")
      (footprint "eagle-import:C0603")
      (libsource (lib "eagle-import") (part "C-USC0603"))
    )
    (comp (ref "C34")
      (value "560p")
      (footprint "eagle-import:C0603")
      (libsource (lib "eagle-import") (part "C-USC0603"))
    )
    (comp (ref "C35")
      (value "100n")
      (footprint "eagle-import:C0603")
      (libsource (lib "eagle-import") (part "C-USC0603"))
    )
    (comp (ref "D7")
      (value "1N4148")
      (footprint "eagle-import:SOD323-W")
      (libsource (lib "eagle-import") (part "DIODE-SOD323-W"))
    )
    (comp (ref "D8")
      (value "1N4148")
      (footprint "eagle-import:SOD323-W")
      (libsource (lib "eagle-import") (part "DIODE-SOD323-W"))
    )
    (comp (ref "D9")
      (value "1N4148")
      (footprint "eagle-import:SOD323-W")
      (libsource (lib "eagle-import") (part "DIODE-SOD323-W"))
    )
    (comp (ref "D15")
      (value "1N4148")
      (footprint "eagle-import:SOD323-W")
      (libsource (lib "eagle-import") (part "DIODE-SOD323-W"))
    )
    (comp (ref "IC6")
      (value "TL074D")
      (footprint "eagle-import:SO14")
      (libsource (lib "eagle-import") (part "TL074D"))
    )
    (comp (ref "IC7")
      (value "TL074D")
      (footprint "eagle-import:SO14")
      (libsource (lib "eagle-import") (part "TL074D"))
    )
    (comp (ref "IC8")
      (value "V2164SZ")
      (footprint "eagle-import:SOIC16N")
      (libsource (lib "eagle-import") (part "SSM2164S"))
    )
    (comp (ref "J3")
      (value "PJ301_THONKICONN6")
      (footprint "eagle-import:WQP_PJ_301M6")
      (libsource (lib "eagle-import") (part "PJ301_THONKICONN6"))
    )
    (comp (ref "J4")
      (value "PJ301_THONKICONN6")
      (footprint "eagle-import:WQP_PJ_301M6")
      (libsource (lib "eagle-import") (part "PJ301_THONKICONN6"))
    )
    (comp (ref "J5")
      (value "PJ301_THONKICONN6")
      (footprint "eagle-import:WQP_PJ_301M6")
      (libsource (lib "eagle-import") (part "PJ301_THONKICONN6"))
    )
    (comp (ref "JP5")
      (value "M03PTH")
      (footprint "eagle-import:1X03")
      (libsource (lib "eagle-import") (part "M03PTH"))
    )
    (comp (ref "JP7")
      (value "M03PTH")
      (footprint "eagle-import:1X03")
      (libsource (lib "eagle-import") (part "M03PTH"))
    )
    (comp (ref "R34")
      (value "10kB")
      (footprint "eagle-import:ALPS_POT_VERTICAL_PS")
      (libsource (lib "eagle-import") (part "POT_USVERTICAL_PS"))
    )
    (comp (ref "R35")
      (value "100k")
      (footprint "eagle-import:R0603")
      (libsource (lib "eagle-import") (part "R-US_R0603"))
    )
    (comp (ref "R36")
      (value "10kB")
      (footprint "eagle-import:ALPS_POT_VERTICAL_PS")
      (libsource (lib "eagle-import") (part "POT_USVERTICAL_PS"))
    )
    (comp (ref "R37")
      (value "100k")
      (footprint "eagle-import:R0603")
      (libsource (lib "eagle-import") (part "R-US_R0603"))
    )
    (comp (ref "R38")
      (value "100k")
      (footprint "eagle-import:R0603")
      (libsource (lib "eagle-import") (part "R-US_R0603"))
    )
    (comp (ref "R39")
      (value "100k")
      (footprint "eagle-import:R0603")
      (libsource (lib "eagle-import") (part "R-US_R0603"))
    )
    (comp (ref "R40")
      (value "100k")
      (footprint "eagle-import:R0603")
      (libsource (lib "eagle-import") (part "R-US_R0603"))
    )
    (comp (ref "R41")
      (value "100k")
      (footprint "eagle-import:R0603")
      (libsource (lib "eagle-import") (part "R-US_R0603"))
    )
    (comp (ref "R42")
      (value "10kB")
      (footprint "eagle-import:ALPS_POT_VERTICAL")
      (libsource (lib "eagle-import") (part "POT_USVERTICAL"))
    )
    (comp (ref "R43")
      (value "100k")
      (footprint "eagle-import:R0603")
      (libsource (lib "eagle-import") (part "R-US_R0603"))
    )
    (comp (ref "R44")
      (value "120k")
      (footprint "eagle-import:R0603")
      (libsource (lib "eagle-import") (part "R-US_R0603"))
    )
    (comp (ref "R45")
      (value "120k")
      (footprint "eagle-import:R0603")
      (libsource (lib "eagle-import") (part "R-US_R0603"))
    )
    (comp (ref "R46")
      (value "200k")
      (footprint "eagle-import:R0603")
      (libsource (lib "eagle-import") (part "R-US_R0603"))
    )
    (comp (ref "R47")
      (value "100k")
      (footprint "eagle-import:R0603")
      (libsource (lib "eagle-import") (part "R-US_R0603"))
    )
    (comp (ref "R48")
      (value "100k")
      (footprint "eagle-import:R0603")
      (libsource (lib "eagle-import") (part "R-US_R0603"))
    )
    (comp (ref "R49")
      (value "100k")
      (footprint "eagle-import:R0603")
      (libsource (lib "eagle-import") (part "R-US_R0603"))
    )
    (comp (ref "R50")
      (value "12k")
      (footprint "eagle-import:R0603")
      (libsource (lib "eagle-import") (part "R-US_R0603"))
    )
    (comp (ref "R51")
      (value "18k")
      (footprint "eagle-import:R0603")
      (libsource (lib "eagle-import") (part "R-US_R0603"))
    )
    (comp (ref "R52")
      (value "100k")
      (footprint "eagle-import:R0603")
      (libsource (lib "eagle-import") (part "R-US_R0603"))
    )
    (comp (ref "R53")
      (value "100k")
      (footprint "eagle-import:R0603")
      (libsource (lib "eagle-import") (part "R-US_R0603"))
    )
    (comp (ref "R54")
      (value "200k")
      (footprint "eagle-import:R0603")
      (libsource (lib "eagle-import") (part "R-US_R0603"))
    )
    (comp (ref "R55")
      (value "100k")
      (footprint "eagle-import:R0603")
      (libsource (lib "eagle-import") (part "R-US_R0603"))
    )
    (comp (ref "R56")
      (value "510")
      (footprint "eagle-import:R0603")
      (libsource (lib "eagle-import") (part "R-US_R0603"))
    )
    (comp (ref "R57")
      (value "510")
      (footprint "eagle-import:R0603")
      (libsource (lib "eagle-import") (part "R-US_R0603"))
    )
    (comp (ref "R58")
      (value "100k")
      (footprint "eagle-import:R0603")
      (libsource (lib "eagle-import") (part "R-US_R0603"))
    )
    (comp (ref "R59")
      (value "100k")
      (footprint "eagle-import:R0603")
      (libsource (lib "eagle-import") (part "R-US_R0603"))
    )
    (comp (ref "R60")
      (value "22k")
      (footprint "eagle-import:R0603")
      (libsource (lib "eagle-import") (part "R-US_R0603"))
    )
    (comp (ref "R61")
      (value "510")
      (footprint "eagle-import:R0603")
      (libsource (lib "eagle-import") (part "R-US_R0603"))
    )
    (comp (ref "R62")
      (value "150k")
      (footprint "eagle-import:R0603")
      (libsource (lib "eagle-import") (part "R-US_R0603"))
    )
    (comp (ref "R63")
      (value "1.5M")
      (footprint "eagle-import:R0603")
      (libsource (lib "eagle-import") (part "R-US_R0603"))
    )
    (comp (ref "R64")
      (value "510")
      (footprint "eagle-import:R0603")
      (libsource (lib "eagle-import") (part "R-US_R0603"))
    )
    (comp (ref "R66")
      (value "100k")
      (footprint "eagle-import:R0603")
      (libsource (lib "eagle-import") (part "R-US_R0603"))
    )
    (comp (ref "R67")
      (value "100k")
      (footprint "eagle-import:R0603")
      (libsource (lib "eagle-import") (part "R-US_R0603"))
    )
  )
  (nets
    (net (code "1") (name "AREF_+10") (class "Default")
      (node (ref "C3") (pin "1") (pinfunction "1_1") (pintype "passive"))
      (node (ref "IC1") (pin "1") (pinfunction "C_1") (pintype "passive"))
      (node (ref "R1") (pin "2") (pinfunction "2_2") (pintype "passive"))
      (node (ref "R118") (pin "2") (pinfunction "2_2") (pintype "passive"))
      (node (ref "R121") (pin "2") (pinfunction "2_2") (pintype "passive"))
      (node (ref "R28") (pin "1") (pinfunction "1_1") (pintype "passive"))
      (node (ref "R29") (pin "1") (pinfunction "1_1") (pintype "passive"))
      (node (ref "R46") (pin "1") (pinfunction "1_1") (pintype "passive"))
      (node (ref "R63") (pin "1") (pinfunction "1_1") (pintype "passive"))
      (node (ref "R80") (pin "1") (pinfunction "1_1") (pintype "passive"))
      (node (ref "R96") (pin "1") (pinfunction "1_1") (pintype "passive"))
    )
    (net (code "2") (name "AREF_-10") (class "Default")
      (node (ref "C4") (pin "1") (pinfunction "1_1") (pintype "passive"))
      (node (ref "IC2") (pin "2") (pinfunction "A_2") (pintype "passive"))
      (node (ref "R108") (pin "1") (pinfunction "1_1") (pintype "passive"))
      (node (ref "R109") (pin "1") (pinfunction "1_1") (pintype "passive"))
      (node (ref "R12") (pin "1") (pinfunction "1_1") (pintype "passive"))
      (node (ref "R2") (pin "2") (pinfunction "2_2") (pintype "passive"))
      (node (ref "R43") (pin "1") (pinfunction "1_1") (pintype "passive"))
      (node (ref "R49") (pin "1") (pinfunction "1_1") (pintype "passive"))
      (node (ref "R5") (pin "1") (pinfunction "1_1") (pintype "passive"))
      (node (ref "R54") (pin "1") (pinfunction "1_1") (pintype "passive"))
      (node (ref "R70") (pin "1") (pinfunction "1_1") (pintype "passive"))
      (node (ref "R77") (pin "1") (pinfunction "1_1") (pintype "passive"))
      (node (ref "R83") (pin "1") (pinfunction "1_1") (pintype "passive"))
    )
    (net (code "3") (name "BP_1") (class "Default")
      (node (ref "C40") (pin "2") (pinfunction "2_2") (pintype "passive"))
      (node (ref "IC9") (pin "7") (pinfunction "OUT_7") (pintype "output"))
      (node (ref "JP13") (pin "1") (pinfunction "1_1") (pintype "passive"))
      (node (ref "R87") (pin "1") (pinfunction "1_1") (pintype "passive"))
      (node (ref "R98") (pin "1") (pinfunction "1_1") (pintype "passive"))
    )
    (net (code "4") (name "BP_2") (class "Default")
      (node (ref "C25") (pin "2") (pinfunction "2_2") (pintype "passive"))
      (node (ref "IC6") (pin "7") (pinfunction "OUT_7") (pintype "output"))
      (node (ref "JP5") (pin "1") (pinfunction "1_1") (pintype "passive"))
      (node (ref "R53") (pin "1") (pinfunction "1_1") (pintype "passive"))
      (node (ref "R66") (pin "1") (pinfunction "1_1") (pintype "passive"))
    )
    (net (code "5") (name "F_GLOBAL") (class "Default")
      (node (ref "J11") (pin "P3") (pinfunction "3_P3") (pintype "passive"))
      (node (ref "R47") (pin "1") (pinfunction "1_1") (pintype "passive"))
      (node (ref "R7") (pin "1") (pinfunction "1_1") (pintype "passive"))
      (node (ref "R8") (pin "1") (pinfunction "1_1") (pintype "passive"))
      (node (ref "R81") (pin "1") (pinfunction "1_1") (pintype "passive"))
    )
    (net (code "6") (name "GAIN_GLOBAL") (class "Default")
      (node (ref "J12") (pin "P3") (pinfunction "3_P3") (pintype "passive"))
      (node (ref "R26") (pin "1") (pinfunction "1_1") (pintype "passive"))
      (node (ref "R31") (pin "1") (pinfunction "1_1") (pintype "passive"))
      (node (ref "R44") (pin "1") (pinfunction "1_1") (pintype "passive"))
      (node (ref "R79") (pin "1") (pinfunction "1_1") (pintype "passive"))
    )
    (net (code "7") (name "GND") (class "Default")
      (node (ref "C1") (pin "-") (pinfunction "-_-") (pintype "passive"))
      (node (ref "C12") (pin "2") (pinfunction "2_2") (pintype "passive"))
      (node (ref "C13") (pin "1") (pinfunction "1_1") (pintype "passive"))
      (node (ref "C14") (pin "2") (pinfunction "2_2") (pintype "passive"))
      (node (ref "C15") (pin "2") (pinfunction "2_2") (pintype "passive"))
      (node (ref "C18") (pin "2") (pinfunction "2_2") (pintype "passive"))
      (node (ref "C19") (pin "2") (pinfunction "2_2") (pintype "passive"))
      (node (ref "C2") (pin "+") (pinfunction "+_+") (pintype "passive"))
      (node (ref "C20") (pin "1") (pinfunction "1_1") (pintype "passive"))
      (node (ref "C21") (pin "2") (pinfunction "2_2") (pintype "passive"))
      (node (ref "C22") (pin "1") (pinfunction "1_1") (pintype "passive"))
      (node (ref "C27") (pin "2") (pinfunction "2_2") (pintype "passive"))
      (node (ref "C28") (pin "1") (pinfunction "1_1") (pintype "passive"))
      (node (ref "C29") (pin "2") (pinfunction "2_2") (pintype "passive"))
      (node (ref "C3") (pin "2") (pinfunction "2_2") (pintype "passive"))
      (node (ref "C30") (pin "2") (pinfunction "2_2") (pintype "passive"))
      (node (ref "C31") (pin "2") (pinfunction "2_2") (pintype "passive"))
      (node (ref "C33") (pin "2") (pinfunction "2_2") (pintype "passive"))
      (node (ref "C34") (pin "2") (pinfunction "2_2") (pintype "passive"))
      (node (ref "C35") (pin "1") (pinfunction "1_1") (pintype "passive"))
      (node (ref "C36") (pin "2") (pinfunction "2_2") (pintype "passive"))
      (node (ref "C37") (pin "1") (pinfunction "1_1") (pintype "passive"))
      (node (ref "C4") (pin "2") (pinfunction "2_2") (pintype "passive"))
      (node (ref "C42") (pin "2") (pinfunction "2_2") (pintype "passive"))
      (node (ref "C43") (pin "2") (pinfunction "2_2") (pintype "passive"))
      (node (ref "C44") (pin "1") (pinfunction "1_1") (pintype "passive"))
      (node (ref "C45") (pin "2") (pinfunction "2_2") (pintype "passive"))
      (node (ref "C47") (pin "2") (pinfunction "2_2") (pintype "passive"))
      (node (ref "C48") (pin "2") (pinfunction "2_2") (pintype "passive"))
      (node (ref "C49") (pin "2") (pinfunction "2_2") (pintype "passive"))
      (node (ref "C5") (pin "2") (pinfunction "2_2") (pintype "passive"))
      (node (ref "C50") (pin "2") (pinfunction "2_2") (pintype "passive"))
      (node (ref "C51") (pin "1") (pinfunction "1_1") (pintype "passive"))
      (node (ref "C52") (pin "2") (pinfunction "2_2") (pintype "passive"))
      (node (ref "C53") (pin "1") (pinfunction "1_1") (pintype "passive"))
      (node (ref "C54") (pin "1") (pinfunction "1_1") (pintype "passive"))
      (node (ref "C55") (pin "2") (pinfunction "2_2") (pintype "passive"))
      (node (ref "C56") (pin "2") (pinfunction "2_2") (pintype "passive"))
      (node (ref "C58") (pin "-") (pinfunction "-_-") (pintype "passive"))
      (node (ref "C8") (pin "1") (pinfunction "1_1") (pintype "passive"))
      (node (ref "C9") (pin "2") (pinfunction "2_2") (pintype "passive"))
      (node (ref "D1") (pin "C") (pinfunction "C_C") (pintype "passive"))
      (node (ref "D10") (pin "A") (pinfunction "A_A") (pintype "passive"))
      (node (ref "D12") (pin "A") (pinfunction "A_A") (pintype "passive"))
      (node (ref "D3") (pin "A") (pinfunction "A_A") (pintype "passive"))
      (node (ref "D4") (pin "A") (pinfunction "A_A") (pintype "passive"))
      (node (ref "D5") (pin "A") (pinfunction "A_A") (pintype "passive"))
      (node (ref "D6") (pin "A") (pinfunction "A_A") (pintype "passive"))
      (node (ref "D7") (pin "A") (pinfunction "A_A") (pintype "passive"))
      (node (ref "D9") (pin "A") (pinfunction "A_A") (pintype "passive"))
      (node (ref "IC1") (pin "2") (pinfunction "A_2") (pintype "passive"))
      (node (ref "IC10") (pin "10") (pinfunction "+IN_10") (pintype "input"))
      (node (ref "IC10") (pin "12") (pinfunction "+IN_12") (pintype "input"))
      (node (ref "IC10") (pin "3") (pinfunction "+IN_3") (pintype "input"))
      (node (ref "IC10") (pin "5") (pinfunction "+IN_5") (pintype "input"))
      (node (ref "IC11") (pin "8") (pinfunction "GND_8") (pintype "power_in"))
      (node (ref "IC12") (pin "3") (pinfunction "+IN_3") (pintype "input"))
      (node (ref "IC12") (pin "5") (pinfunction "+IN_5") (pintype "input"))
      (node (ref "IC13") (pin "3") (pinfunction "+IN_3") (pintype "input"))
      (node (ref "IC13") (pin "5") (pinfunction "+IN_5") (pintype "input"))
      (node (ref "IC14") (pin "4") (pinfunction "V-_4") (pintype "power_in"))
      (node (ref "IC2") (pin "1") (pinfunction "C_1") (pintype "passive"))
      (node (ref "IC3") (pin "3") (pinfunction "+IN_3") (pintype "input"))
      (node (ref "IC3") (pin "5") (pinfunction "+IN_5") (pintype "input"))
      (node (ref "IC4") (pin "10") (pinfunction "+IN_10") (pintype "input"))
      (node (ref "IC4") (pin "12") (pinfunction "+IN_12") (pintype "input"))
      (node (ref "IC4") (pin "3") (pinfunction "+IN_3") (pintype "input"))
      (node (ref "IC4") (pin "5") (pinfunction "+IN_5") (pintype "input"))
      (node (ref "IC5") (pin "8") (pinfunction "GND_8") (pintype "power_in"))
      (node (ref "IC6") (pin "10") (pinfunction "+IN_10") (pintype "input"))
      (node (ref "IC6") (pin "12") (pinfunction "+IN_12") (pintype "input"))
      (node (ref "IC6") (pin "3") (pinfunction "+IN_3") (pintype "input"))
      (node (ref "IC6") (pin "5") (pinfunction "+IN_5") (pintype "input"))
      (node (ref "IC7") (pin "10") (pinfunction "+IN_10") (pintype "input"))
      (node (ref "IC7") (pin "12") (pinfunction "+IN_12") (pintype "input"))
      (node (ref "IC7") (pin "3") (pinfunction "+IN_3") (pintype "input"))
      (node (ref "IC7") (pin "5") (pinfunction "+IN_5") (pintype "input"))
      (node (ref "IC8") (pin "8") (pinfunction "GND_8") (pintype "power_in"))
      (node (ref "IC9") (pin "10") (pinfunction "+IN_10") (pintype "input"))
      (node (ref "IC9") (pin "12") (pinfunction "+IN_12") (pintype "input"))
      (node (ref "IC9") (pin "3") (pinfunction "+IN_3") (pintype "input"))
      (node (ref "IC9") (pin "5") (pinfunction "+IN_5") (pintype "input"))
      (node (ref "J1") (pin "P1") (pinfunction "1_P1") (pintype "passive"))
      (node (ref "J10") (pin "P1") (pinfunction "1_P1") (pintype "passive"))
      (node (ref "J11") (pin "P1") (pinfunction "1_P1") (pintype "passive"))
      (node (ref "J12") (pin "P1") (pinfunction "1_P1") (pintype "passive"))
      (node (ref "J13") (pin "P1") (pinfunction "1_P1") (pintype "passive"))
      (node (ref "J14") (pin "P1") (pinfunction "1_P1") (pintype "passive"))
      (node (ref "J2") (pin "P1") (pinfunction "1_P1") (pintype "passive"))
      (node (ref "J3") (pin "P1") (pinfunction "1_P1") (pintype "passive"))
      (node (ref "J4") (pin "P1") (pinfunction "1_P1") (pintype "passive"))
      (node (ref "J5") (pin "P1") (pinfunction "1_P1") (pintype "passive"))
      (node (ref "J6") (pin "P1") (pinfunction "1_P1") (pintype "passive"))
      (node (ref "J7") (pin "P1") (pinfunction "1_P1") (pintype "passive"))
      (node (ref "J8") (pin "P1") (pinfunction "1_P1") (pintype "passive"))
      (node (ref "J9") (pin "P1") (pinfunction "1_P1") (pintype "passive"))
      (node (ref "JP11") (pin "3") (pinfunction "3_3") (pintype "passive"))
      (node (ref "JP11") (pin "4") (pinfunction "4_4") (pintype "passive"))
      (node (ref "JP11") (pin "5") (pinfunction "5_5") (pintype "passive"))
      (node (ref "JP11") (pin "6") (pinfunction "6_6") (pintype "passive"))
      (node (ref "JP11") (pin "7") (pinfunction "7_7") (pintype "passive"))
      (node (ref "JP11") (pin "8") (pinfunction "8_8") (pintype "passive"))
      (node (ref "JP6") (pin "1") (pinfunction "1_1") (pintype "passive"))
      (node (ref "JP6") (pin "2") (pinfunction "2_2") (pintype "passive"))
      (node (ref "JP6") (pin "3") (pinfunction "3_3") (pintype "passive"))
      (node (ref "JP7") (pin "1") (pinfunction "1_1") (pintype "passive"))
      (node (ref "JP7") (pin "2") (pinfunction "2_2") (pintype "passive"))
      (node (ref "JP7") (pin "3") (pinfunction "3_3") (pintype "passive"))
      (node (ref "Q1") (pin "E") (pinfunction "E_E") (pintype "passive"))
      (node (ref "R100") (pin "P$1") (pinfunction "E_P$1") (pintype "passive"))
      (node (ref "R101") (pin "P$1") (pinfunction "E_P$1") (pintype "passive"))
      (node (ref "R116") (pin "1") (pinfunction "1_1") (pintype "passive"))
      (node (ref "R117") (pin "1") (pinfunction "1_1") (pintype "passive"))
      (node (ref "R120") (pin "1") (pinfunction "1_1") (pintype "passive"))
      (node (ref "R3") (pin "P$1") (pinfunction "E_P$1") (pintype "passive"))
      (node (ref "R34") (pin "P$1") (pinfunction "E_P$1") (pintype "passive"))
      (node (ref "R36") (pin "P$1") (pinfunction "E_P$1") (pintype "passive"))
      (node (ref "R4") (pin "P$1") (pinfunction "E_P$1") (pintype "passive"))
      (node (ref "R42") (pin "P$3") (pinfunction "A_P$3") (pintype "passive"))
      (node (ref "R65") (pin "P$3") (pinfunction "A_P$3") (pintype "passive"))
      (node (ref "R68") (pin "P$1") (pinfunction "E_P$1") (pintype "passive"))
      (node (ref "R69") (pin "P$1") (pinfunction "E_P$1") (pintype "passive"))
    )
    (net (code "8") (name "HP_1") (class "Default")
      (node (ref "IC9") (pin "1") (pinfunction "OUT_1") (pintype "output"))
      (node (ref "JP13") (pin "3") (pinfunction "3_3") (pintype "passive"))
      (node (ref "R75") (pin "2") (pinfunction "2_2") (pintype "passive"))
      (node (ref "R86") (pin "1") (pinfunction "1_1") (pintype "passive"))
    )
    (net (code "9") (name "HP_2") (class "Default")
      (node (ref "IC6") (pin "1") (pinfunction "OUT_1") (pintype "output"))
      (node (ref "JP5") (pin "3") (pinfunction "3_3") (pintype "passive"))
      (node (ref "R40") (pin "2") (pinfunction "2_2") (pintype "passive"))
      (node (ref "R52") (pin "1") (pinfunction "1_1") (pintype "passive"))
    )
    (net (code "10") (name "IN") (class "Default")
      (node (ref "IC12") (pin "7") (pinfunction "OUT_7") (pintype "output"))
      (node (ref "JP12") (pin "3") (pinfunction "3_3") (pintype "passive"))
      (node (ref "R103") (pin "2") (pinfunction "2_2") (pintype "passive"))
      (node (ref "R15") (pin "1") (pinfunction "1_1") (pintype "passive"))
      (node (ref "R16") (pin "1") (pinfunction "1_1") (pintype "passive"))
      (node (ref "R17") (pin "1") (pinfunction "1_1") (pintype "passive"))
      (node (ref "R37") (pin "1") (pinfunction "1_1") (pintype "passive"))
      (node (ref "R72") (pin "1") (pinfunction "1_1") (pintype "passive"))
    )
    (net (code "11") (name "MINUS_BUS") (class "Default")
      (node (ref "IC11") (pin "12") (pinfunction "OUT_12") (pintype "output"))
      (node (ref "IC13") (pin "2") (pinfunction "-IN_2") (pintype "input"))
      (node (ref "IC5") (pin "5") (pinfunction "OUT_5") (pintype "output"))
      (node (ref "IC8") (pin "12") (pinfunction "OUT_12") (pintype "output"))
      (node (ref "R104") (pin "2") (pinfunction "2_2") (pintype "passive"))
      (node (ref "R107") (pin "1") (pinfunction "1_1") (pintype "passive"))
      (node (ref "R19") (pin "2") (pinfunction "2_2") (pintype "passive"))
    )
    (net (code "12") (name "Net-(C14-Pad1)") (class "Default")
      (node (ref "C14") (pin "1") (pinfunction "1_1") (pintype "passive"))
      (node (ref "R21") (pin "1") (pinfunction "1_1") (pintype "passive"))
    )
    (net (code "13") (name "Net-(C15-Pad1)") (class "Default")
      (node (ref "C15") (pin "1") (pinfunction "1_1") (pintype "passive"))
      (node (ref "R20") (pin "1") (pinfunction "1_1") (pintype "passive"))
    )
    (net (code "14") (name "Net-(C18-Pad1)") (class "Default")
      (node (ref "C18") (pin "1") (pinfunction "1_1") (pintype "passive"))
      (node (ref "R24") (pin "1") (pinfunction "1_1") (pintype "passive"))
    )
    (net (code "15") (name "Net-(C19-Pad1)") (class "Default")
      (node (ref "C19") (pin "1") (pinfunction "1_1") (pintype "passive"))
      (node (ref "R25") (pin "1") (pinfunction "1_1") (pintype "passive"))
    )
    (net (code "16") (name "Net-(C29-Pad1)") (class "Default")
      (node (ref "C29") (pin "1") (pinfunction "1_1") (pintype "passive"))
      (node (ref "R56") (pin "1") (pinfunction "1_1") (pintype "passive"))
    )
    (net (code "17") (name "Net-(C30-Pad1)") (class "Default")
      (node (ref "C30") (pin "1") (pinfunction "1_1") (pintype "passive"))
      (node (ref "R57") (pin "1") (pinfunction "1_1") (pintype "passive"))
    )
    (net (code "18") (name "Net-(C33-Pad1)") (class "Default")
      (node (ref "C33") (pin "1") (pinfunction "1_1") (pintype "passive"))
      (node (ref "R61") (pin "1") (pinfunction "1_1") (pintype "passive"))
    )
    (net (code "19") (name "Net-(C34-Pad1)") (class "Default")
      (node (ref "C34") (pin "1") (pinfunction "1_1") (pintype "passive"))
      (node (ref "R64") (pin "1") (pinfunction "1_1") (pintype "passive"))
    )
    (net (code "20") (name "Net-(C45-Pad1)") (class "Default")
      (node (ref "C45") (pin "1") (pinfunction "1_1") (pintype "passive"))
      (node (ref "R89") (pin "1") (pinfunction "1_1") (pintype "passive"))
    )
    (net (code "21") (name "Net-(C47-Pad1)") (class "Default")
      (node (ref "C47") (pin "1") (pinfunction "1_1") (pintype "passive"))
      (node (ref "R90") (pin "1") (pinfunction "1_1") (pintype "passive"))
    )
    (net (code "22") (name "Net-(C48-Pad1)") (class "Default")
      (node (ref "C48") (pin "1") (pinfunction "1_1") (pintype "passive"))
      (node (ref "R94") (pin "1") (pinfunction "1_1") (pintype "passive"))
    )
    (net (code "23") (name "Net-(C49-Pad1)") (class "Default")
      (node (ref "C49") (pin "1") (pinfunction "1_1") (pintype "passive"))
      (node (ref "R97") (pin "1") (pinfunction "1_1") (pintype "passive"))
    )
    (net (code "24") (name "Net-(C55-Pad1)") (class "Default")
      (node (ref "C55") (pin "1") (pinfunction "1_1") (pintype "passive"))
      (node (ref "R113") (pin "2") (pinfunction "2_2") (pintype "passive"))
      (node (ref "R114") (pin "1") (pinfunction "1_1") (pintype "passive"))
    )
    (net (code "25") (name "Net-(C57-Pad1)") (class "Default")
      (node (ref "C57") (pin "1") (pinfunction "1_1") (pintype "passive"))
      (node (ref "R115") (pin "1") (pinfunction "1_1") (pintype "passive"))
    )
    (net (code "26") (name "Net-(D2-PadA)") (class "Default")
      (node (ref "D2") (pin "A") (pinfunction "A_A") (pintype "passive"))
      (node (ref "JP11") (pin "1") (pinfunction "1_1") (pintype "passive"))
      (node (ref "JP11") (pin "2") (pinfunction "2_2") (pintype "passive"))
    )
    (net (code "27") (name "Net-(D13-PadC)") (class "Default")
      (node (ref "D13") (pin "C") (pinfunction "C_C") (pintype "passive"))
      (node (ref "D14") (pin "C") (pinfunction "C_C") (pintype "passive"))
      (node (ref "R113") (pin "1") (pinfunction "1_1") (pintype "passive"))
    )
    (net (code "28") (name "Net-(IC3A--IN)") (class "Default")
      (node (ref "C6") (pin "1") (pinfunction "1_1") (pintype "passive"))
      (node (ref "IC3") (pin "2") (pinfunction "-IN_2") (pintype "input"))
      (node (ref "IC5") (pin "4") (pinfunction "OUT_4") (pintype "output"))
    )
    (net (code "29") (name "Net-(IC3A-OUT)") (class "Default")
      (node (ref "C6") (pin "2") (pinfunction "2_2") (pintype "passive"))
      (node (ref "IC3") (pin "1") (pinfunction "OUT_1") (pintype "output"))
      (node (ref "R11") (pin "2") (pinfunction "2_2") (pintype "passive"))
      (node (ref "R32") (pin "1") (pinfunction "1_1") (pintype "passive"))
      (node (ref "R33") (pin "1") (pinfunction "1_1") (pintype "passive"))
    )
    (net (code "30") (name "Net-(IC3B--IN)") (class "Default")
      (node (ref "C7") (pin "1") (pinfunction "1_1") (pintype "passive"))
      (node (ref "IC3") (pin "6") (pinfunction "-IN_6") (pintype "input"))
      (node (ref "IC5") (pin "13") (pinfunction "OUT_13") (pintype "output"))
    )
    (net (code "31") (name "Net-(IC3B-OUT)") (class "Default")
      (node (ref "C7") (pin "2") (pinfunction "2_2") (pintype "passive"))
      (node (ref "IC3") (pin "7") (pinfunction "OUT_7") (pintype "output"))
      (node (ref "R10") (pin "2") (pinfunction "2_2") (pintype "passive"))
      (node (ref "R18") (pin "1") (pinfunction "1_1") (pintype "passive"))
      (node (ref "R19") (pin "1") (pinfunction "1_1") (pintype "passive"))
    )
    (net (code "32") (name "Net-(IC4A--IN)") (class "Default")
      (node (ref "C10") (pin "2") (pinfunction "2_2") (pintype "passive"))
      (node (ref "IC4") (pin "2") (pinfunction "-IN_2") (pintype "input"))
      (node (ref "R13") (pin "1") (pinfunction "1_1") (pintype "passive"))
      (node (ref "R3") (pin "P$3") (pinfunction "A_P$3") (pintype "passive"))
      (node (ref "R6") (pin "2") (pinfunction "2_2") (pintype "passive"))
      (node (ref "R7") (pin "2") (pinfunction "2_2") (pintype "passive"))
    )
    (net (code "33") (name "Net-(IC4A-OUT)") (class "Default")
      (node (ref "C10") (pin "1") (pinfunction "1_1") (pintype "passive"))
      (node (ref "D3") (pin "C") (pinfunction "C_C") (pintype "passive"))
      (node (ref "IC4") (pin "1") (pinfunction "OUT_1") (pintype "output"))
      (node (ref "IC5") (pin "14") (pinfunction "CTRL_14") (pintype "input"))
      (node (ref "R13") (pin "2") (pinfunction "2_2") (pintype "passive"))
    )
    (net (code "34") (name "Net-(IC4B--IN)") (class "Default")
      (node (ref "C16") (pin "2") (pinfunction "2_2") (pintype "passive"))
      (node (ref "IC4") (pin "6") (pinfunction "-IN_6") (pintype "input"))
      (node (ref "R101") (pin "P$3") (pinfunction "A_P$3") (pintype "passive"))
      (node (ref "R22") (pin "1") (pinfunction "1_1") (pintype "passive"))
      (node (ref "R26") (pin "2") (pinfunction "2_2") (pintype "passive"))
      (node (ref "R27") (pin "2") (pinfunction "2_2") (pintype "passive"))
      (node (ref "R28") (pin "2") (pinfunction "2_2") (pintype "passive"))
    )
    (net (code "35") (name "Net-(IC4B-OUT)") (class "Default")
      (node (ref "C16") (pin "1") (pinfunction "1_1") (pintype "passive"))
      (node (ref "D6") (pin "C") (pinfunction "C_C") (pintype "passive"))
      (node (ref "IC4") (pin "7") (pinfunction "OUT_7") (pintype "output"))
      (node (ref "IC5") (pin "6") (pinfunction "CTRL_6") (pintype "input"))
      (node (ref "R22") (pin "2") (pinfunction "2_2") (pintype "passive"))
    )
    (net (code "36") (name "Net-(IC4C--IN)") (class "Default")
      (node (ref "C17") (pin "2") (pinfunction "2_2") (pintype "passive"))
      (node (ref "IC4") (pin "9") (pinfunction "-IN_9") (pintype "input"))
      (node (ref "R23") (pin "1") (pinfunction "1_1") (pintype "passive"))
      (node (ref "R29") (pin "2") (pinfunction "2_2") (pintype "passive"))
      (node (ref "R30") (pin "2") (pinfunction "2_2") (pintype "passive"))
      (node (ref "R31") (pin "2") (pinfunction "2_2") (pintype "passive"))
      (node (ref "R4") (pin "P$3") (pinfunction "A_P$3") (pintype "passive"))
    )
    (net (code "37") (name "Net-(IC4C-OUT)") (class "Default")
      (node (ref "C17") (pin "1") (pinfunction "1_1") (pintype "passive"))
      (node (ref "D5") (pin "C") (pinfunction "C_C") (pintype "passive"))
      (node (ref "IC4") (pin "8") (pinfunction "OUT_8") (pintype "output"))
      (node (ref "IC5") (pin "11") (pinfunction "CTRL_11") (pintype "input"))
      (node (ref "R23") (pin "2") (pinfunction "2_2") (pintype "passive"))
    )
    (net (code "38") (name "Net-(IC4D--IN)") (class "Default")
      (node (ref "C11") (pin "2") (pinfunction "2_2") (pintype "passive"))
      (node (ref "IC4") (pin "13") (pinfunction "-IN_13") (pintype "input"))
      (node (ref "R100") (pin "P$3") (pinfunction "A_P$3") (pintype "passive"))
      (node (ref "R14") (pin "1") (pinfunction "1_1") (pintype "passive"))
      (node (ref "R8") (pin "2") (pinfunction "2_2") (pintype "passive"))
      (node (ref "R9") (pin "2") (pinfunction "2_2") (pintype "passive"))
    )
    (net (code "39") (name "Net-(IC4D-OUT)") (class "Default")
      (node (ref "C11") (pin "1") (pinfunction "1_1") (pintype "passive"))
      (node (ref "D4") (pin "C") (pinfunction "C_C") (pintype "passive"))
      (node (ref "IC4") (pin "14") (pinfunction "OUT_14") (pintype "output"))
      (node (ref "IC5") (pin "3") (pinfunction "CTRL_3") (pintype "input"))
      (node (ref "R14") (pin "2") (pinfunction "2_2") (pintype "passive"))
    )
    (net (code "40") (name "Net-(IC5A-IN)") (class "Default")
      (node (ref "IC5") (pin "2") (pinfunction "IN_2") (pintype "input"))
      (node (ref "R11") (pin "1") (pinfunction "1_1") (pintype "passive"))
      (node (ref "R15") (pin "2") (pinfunction "2_2") (pintype "passive"))
      (node (ref "R20") (pin "2") (pinfunction "2_2") (pintype "passive"))
    )
    (net (code "41") (name "Net-(IC5B-IN)") (class "Default")
      (node (ref "IC5") (pin "7") (pinfunction "IN_7") (pintype "input"))
      (node (ref "R25") (pin "2") (pinfunction "2_2") (pintype "passive"))
      (node (ref "R32") (pin "2") (pinfunction "2_2") (pintype "passive"))
    )
    (net (code "42") (name "Net-(IC5C-IN)") (class "Default")
      (node (ref "IC5") (pin "10") (pinfunction "IN_10") (pintype "input"))
      (node (ref "R17") (pin "2") (pinfunction "2_2") (pintype "passive"))
      (node (ref "R18") (pin "2") (pinfunction "2_2") (pintype "passive"))
      (node (ref "R24") (pin "2") (pinfunction "2_2") (pintype "passive"))
    )
    (net (code "43") (name "Net-(IC5D-IN)") (class "Default")
      (node (ref "IC5") (pin "15") (pinfunction "IN_15") (pintype "input"))
      (node (ref "R10") (pin "1") (pinfunction "1_1") (pintype "passive"))
      (node (ref "R16") (pin "2") (pinfunction "2_2") (pintype "passive"))
      (node (ref "R21") (pin "2") (pinfunction "2_2") (pintype "passive"))
    )
    (net (code "44") (name "Net-(IC6A--IN)") (class "Default")
      (node (ref "IC6") (pin "2") (pinfunction "-IN_2") (pintype "input"))
      (node (ref "R35") (pin "1") (pinfunction "1_1") (pintype "passive"))
      (node (ref "R37") (pin "2") (pinfunction "2_2") (pintype "passive"))
      (node (ref "R38") (pin "1") (pinfunction "1_1") (pintype "passive"))
      (node (ref "R40") (pin "1") (pinfunction "1_1") (pintype "passive"))
    )
    (net (code "45") (name "Net-(IC6B--IN)") (class "Default")
      (node (ref "C25") (pin "1") (pinfunction "1_1") (pintype "passive"))
      (node (ref "IC6") (pin "6") (pinfunction "-IN_6") (pintype "input"))
      (node (ref "IC8") (pin "4") (pinfunction "OUT_4") (pintype "output"))
    )
    (net (code "46") (name "Net-(IC6C--IN)") (class "Default")
      (node (ref "C26") (pin "1") (pinfunction "1_1") (pintype "passive"))
      (node (ref "IC6") (pin "9") (pinfunction "-IN_9") (pintype "input"))
      (node (ref "IC8") (pin "13") (pinfunction "OUT_13") (pintype "output"))
    )
    (net (code "47") (name "Net-(IC6C-OUT)") (class "Default")
      (node (ref "C26") (pin "2") (pinfunction "2_2") (pintype "passive"))
      (node (ref "IC6") (pin "8") (pinfunction "OUT_8") (pintype "output"))
      (node (ref "JP5") (pin "2") (pinfunction "2_2") (pintype "passive"))
      (node (ref "R35") (pin "2") (pinfunction "2_2") (pintype "passive"))
    )
    (net (code "48") (name "Net-(IC6D--IN)") (class "Default")
      (node (ref "IC6") (pin "13") (pinfunction "-IN_13") (pintype "input"))
      (node (ref "IC8") (pin "5") (pinfunction "OUT_5") (pintype "output"))
      (node (ref "R41") (pin "2") (pinfunction "2_2") (pintype "passive"))
    )
    (net (code "49") (name "Net-(IC6D-OUT)") (class "Default")
      (node (ref "IC6") (pin "14") (pinfunction "OUT_14") (pintype "output"))
      (node (ref "R38") (pin "2") (pinfunction "2_2") (pintype "passive"))
      (node (ref "R39") (pin "1") (pinfunction "1_1") (pintype "passive"))
      (node (ref "R55") (pin "1") (pinfunction "1_1") (pintype "passive"))
      (node (ref "R67") (pin "1") (pinfunction "1_1") (pintype "passive"))
    )
    (net (code "50") (name "Net-(IC7A--IN)") (class "Default")
      (node (ref "C23") (pin "2") (pinfunction "2_2") (pintype "passive"))
      (node (ref "IC7") (pin "2") (pinfunction "-IN_2") (pintype "input"))
      (node (ref "R36") (pin "P$3") (pinfunction "A_P$3") (pintype "passive"))
      (node (ref "R44") (pin "2") (pinfunction "2_2") (pintype "passive"))
      (node (ref "R45") (pin "2") (pinfunction "2_2") (pintype "passive"))
      (node (ref "R46") (pin "2") (pinfunction "2_2") (pintype "passive"))
      (node (ref "R50") (pin "1") (pinfunction "1_1") (pintype "passive"))
    )
    (net (code "51") (name "Net-(IC7A-OUT)") (class "Default")
      (node (ref "C23") (pin "1") (pinfunction "1_1") (pintype "passive"))
      (node (ref "D7") (pin "C") (pinfunction "C_C") (pintype "passive"))
      (node (ref "IC7") (pin "1") (pinfunction "OUT_1") (pintype "output"))
      (node (ref "IC8") (pin "11") (pinfunction "CTRL_11") (pintype "input"))
      (node (ref "R50") (pin "2") (pinfunction "2_2") (pintype "passive"))
    )
    (net (code "52") (name "Net-(IC7B--IN)") (class "Default")
      (node (ref "IC7") (pin "6") (pinfunction "-IN_6") (pintype "input"))
      (node (ref "R58") (pin "2") (pinfunction "2_2") (pintype "passive"))
      (node (ref "R59") (pin "1") (pinfunction "1_1") (pintype "passive"))
    )
    (net (code "53") (name "Net-(IC7B-OUT)") (class "Default")
      (node (ref "IC7") (pin "7") (pinfunction "OUT_7") (pintype "output"))
      (node (ref "R59") (pin "2") (pinfunction "2_2") (pintype "passive"))
      (node (ref "R62") (pin "1") (pinfunction "1_1") (pintype "passive"))
    )
    (net (code "54") (name "Net-(IC7C--IN)") (class "Default")
      (node (ref "C32") (pin "2") (pinfunction "2_2") (pintype "passive"))
      (node (ref "IC7") (pin "9") (pinfunction "-IN_9") (pintype "input"))
      (node (ref "R42") (pin "P$1") (pinfunction "E_P$1") (pintype "passive"))
      (node (ref "R60") (pin "1") (pinfunction "1_1") (pintype "passive"))
      (node (ref "R62") (pin "2") (pinfunction "2_2") (pintype "passive"))
      (node (ref "R63") (pin "2") (pinfunction "2_2") (pintype "passive"))
    )
    (net (code "55") (name "Net-(IC7C-OUT)") (class "Default")
      (node (ref "C32") (pin "1") (pinfunction "1_1") (pintype "passive"))
      (node (ref "D9") (pin "C") (pinfunction "C_C") (pintype "passive"))
      (node (ref "IC7") (pin "8") (pinfunction "OUT_8") (pintype "output"))
      (node (ref "IC8") (pin "6") (pinfunction "CTRL_6") (pintype "input"))
      (node (ref "R60") (pin "2") (pinfunction "2_2") (pintype "passive"))
    )
    (net (code "56") (name "Net-(IC7D--IN)") (class "Default")
      (node (ref "C24") (pin "2") (pinfunction "2_2") (pintype "passive"))
      (node (ref "D8") (pin "A") (pinfunction "A_A") (pintype "passive"))
      (node (ref "IC7") (pin "13") (pinfunction "-IN_13") (pintype "input"))
      (node (ref "R34") (pin "P$3") (pinfunction "A_P$3") (pintype "passive"))
      (node (ref "R47") (pin "2") (pinfunction "2_2") (pintype "passive"))
      (node (ref "R48") (pin "2") (pinfunction "2_2") (pintype "passive"))
      (node (ref "R51") (pin "1") (pinfunction "1_1") (pintype "passive"))
    )
    (net (code "57") (name "Net-(IC7D-OUT)") (class "Default")
      (node (ref "D15") (pin "A") (pinfunction "A_A") (pintype "passive"))
      (node (ref "D8") (pin "C") (pinfunction "C_C") (pintype "passive"))
      (node (ref "IC7") (pin "14") (pinfunction "OUT_14") (pintype "output"))
    )
    (net (code "58") (name "Net-(IC8A-CTRL)") (class "Default")
      (node (ref "C24") (pin "1") (pinfunction "1_1") (pintype "passive"))
      (node (ref "D15") (pin "C") (pinfunction "C_C") (pintype "passive"))
      (node (ref "IC8") (pin "14") (pinfunction "CTRL_14") (pintype "input"))
      (node (ref "IC8") (pin "3") (pinfunction "CTRL_3") (pintype "input"))
      (node (ref "R51") (pin "2") (pinfunction "2_2") (pintype "passive"))
    )
    (net (code "59") (name "Net-(IC8A-IN)") (class "Default")
      (node (ref "IC8") (pin "2") (pinfunction "IN_2") (pintype "input"))
      (node (ref "R52") (pin "2") (pinfunction "2_2") (pintype "passive"))
      (node (ref "R56") (pin "2") (pinfunction "2_2") (pintype "passive"))
    )
    (net (code "60") (name "Net-(IC8B-IN)") (class "Default")
      (node (ref "IC8") (pin "7") (pinfunction "IN_7") (pintype "input"))
      (node (ref "R61") (pin "2") (pinfunction "2_2") (pintype "passive"))
      (node (ref "R66") (pin "2") (pinfunction "2_2") (pintype "passive"))
    )
    (net (code "61") (name "Net-(IC8C-IN)") (class "Default")
      (node (ref "IC8") (pin "10") (pinfunction "IN_10") (pintype "input"))
      (node (ref "R64") (pin "2") (pinfunction "2_2") (pintype "passive"))
      (node (ref "R67") (pin "2") (pinfunction "2_2") (pintype "passive"))
    )
    (net (code "62") (name "Net-(IC8D-IN)") (class "Default")
      (node (ref "IC8") (pin "15") (pinfunction "IN_15") (pintype "input"))
      (node (ref "R53") (pin "2") (pinfunction "2_2") (pintype "passive"))
      (node (ref "R57") (pin "2") (pinfunction "2_2") (pintype "passive"))
    )
    (net (code "63") (name "Net-(IC9A--IN)") (class "Default")
      (node (ref "IC9") (pin "2") (pinfunction "-IN_2") (pintype "input"))
      (node (ref "R71") (pin "1") (pinfunction "1_1") (pintype "passive"))
      (node (ref "R72") (pin "2") (pinfunction "2_2") (pintype "passive"))
      (node (ref "R73") (pin "1") (pinfunction "1_1") (pintype "passive"))
      (node (ref "R75") (pin "1") (pinfunction "1_1") (pintype "passive"))
    )
    (net (code "64") (name "Net-(IC9C-OUT)") (class "Default")
      (node (ref "C41") (pin "2") (pinfunction "2_2") (pintype "passive"))
      (node (ref "IC9") (pin "8") (pinfunction "OUT_8") (pintype "output"))
      (node (ref "JP13") (pin "2") (pinfunction "2_2") (pintype "passive"))
      (node (ref "R71") (pin "2") (pinfunction "2_2") (pintype "passive"))
    )
    (net (code "65") (name "Net-(IC9D-OUT)") (class "Default")
      (node (ref "IC9") (pin "14") (pinfunction "OUT_14") (pintype "output"))
      (node (ref "R73") (pin "2") (pinfunction "2_2") (pintype "passive"))
      (node (ref "R74") (pin "1") (pinfunction "1_1") (pintype "passive"))
      (node (ref "R88") (pin "1") (pinfunction "1_1") (pintype "passive"))
      (node (ref "R99") (pin "1") (pinfunction "1_1") (pintype "passive"))
    )
    (net (code "66") (name "Net-(IC10A--IN)") (class "Default")
      (node (ref "C38") (pin "2") (pinfunction "2_2") (pintype "passive"))
      (node (ref "IC10") (pin "2") (pinfunction "-IN_2") (pintype "input"))
      (node (ref "R69") (pin "P$3") (pinfunction "A_P$3") (pintype "passive"))
      (node (ref "R78") (pin "2") (pinfunction "2_2") (pintype "passive"))
      (node (ref "R79") (pin "2") (pinfunction "2_2") (pintype "passive"))
      (node (ref "R80") (pin "2") (pinfunction "2_2") (pintype "passive"))
      (node (ref "R84") (pin "1") (pinfunction "1_1") (pintype "passive"))
    )
    (net (code "67") (name "Net-(IC10A-OUT)") (class "Default")
      (node (ref "C38") (pin "1") (pinfunction "1_1") (pintype "passive"))
      (node (ref "D10") (pin "C") (pinfunction "C_C") (pintype "passive"))
      (node (ref "IC10") (pin "1") (pinfunction "OUT_1") (pintype "output"))
      (node (ref "IC11") (pin "11") (pinfunction "CTRL_11") (pintype "input"))
      (node (ref "R84") (pin "2") (pinfunction "2_2") (pintype "passive"))
    )
    (net (code "68") (name "Net-(IC10B--IN)") (class "Default")
      (node (ref "IC10") (pin "6") (pinfunction "-IN_6") (pintype "input"))
      (node (ref "R91") (pin "2") (pinfunction "2_2") (pintype "passive"))
      (node (ref "R92") (pin "1") (pinfunction "1_1") (pintype "passive"))
    )
    (net (code "69") (name "Net-(IC10B-OUT)") (class "Default")
      (node (ref "IC10") (pin "7") (pinfunction "OUT_7") (pintype "output"))
      (node (ref "R92") (pin "2") (pinfunction "2_2") (pintype "passive"))
      (node (ref "R95") (pin "1") (pinfunction "1_1") (pintype "passive"))
    )
    (net (code "70") (name "Net-(IC10C--IN)") (class "Default")
      (node (ref "C46") (pin "2") (pinfunction "2_2") (pintype "passive"))
      (node (ref "IC10") (pin "9") (pinfunction "-IN_9") (pintype "input"))
      (node (ref "R65") (pin "P$1") (pinfunction "E_P$1") (pintype "passive"))
      (node (ref "R93") (pin "1") (pinfunction "1_1") (pintype "passive"))
      (node (ref "R95") (pin "2") (pinfunction "2_2") (pintype "passive"))
      (node (ref "R96") (pin "2") (pinfunction "2_2") (pintype "passive"))
    )
    (net (code "71") (name "Net-(IC10C-OUT)") (class "Default")
      (node (ref "C46") (pin "1") (pinfunction "1_1") (pintype "passive"))
      (node (ref "D12") (pin "C") (pinfunction "C_C") (pintype "passive"))
      (node (ref "IC10") (pin "8") (pinfunction "OUT_8") (pintype "output"))
      (node (ref "IC11") (pin "6") (pinfunction "CTRL_6") (pintype "input"))
      (node (ref "R93") (pin "2") (pinfunction "2_2") (pintype "passive"))
    )
    (net (code "72") (name "Net-(IC10D--IN)") (class "Default")
      (node (ref "C39") (pin "2") (pinfunction "2_2") (pintype "passive"))
      (node (ref "D11") (pin "A") (pinfunction "A_A") (pintype "passive"))
      (node (ref "IC10") (pin "13") (pinfunction "-IN_13") (pintype "input"))
      (node (ref "R68") (pin "P$3") (pinfunction "A_P$3") (pintype "passive"))
      (node (ref "R81") (pin "2") (pinfunction "2_2") (pintype "passive"))
      (node (ref "R82") (pin "2") (pinfunction "2_2") (pintype "passive"))
      (node (ref "R85") (pin "1") (pinfunction "1_1") (pintype "passive"))
    )
    (net (code "73") (name "Net-(IC10D-OUT)") (class "Default")
      (node (ref "D11") (pin "C") (pinfunction "C_C") (pintype "passive"))
      (node (ref "D16") (pin "A") (pinfunction "A_A") (pintype "passive"))
      (node (ref "IC10") (pin "14") (pinfunction "OUT_14") (pintype "output"))
    )
    (net (code "74") (name "Net-(IC11A-CTRL)") (class "Default")
      (node (ref "C39") (pin "1") (pinfunction "1_1") (pintype "passive"))
      (node (ref "D16") (pin "C") (pinfunction "C_C") (pintype "passive"))
      (node (ref "IC11") (pin "14") (pinfunction "CTRL_14") (pintype "input"))
      (node (ref "IC11") (pin "3") (pinfunction "CTRL_3") (pintype "input"))
      (node (ref "R85") (pin "2") (pinfunction "2_2") (pintype "passive"))
    )
    (net (code "75") (name "Net-(IC11A-IN)") (class "Default")
      (node (ref "IC11") (pin "2") (pinfunction "IN_2") (pintype "input"))
      (node (ref "R86") (pin "2") (pinfunction "2_2") (pintype "passive"))
      (node (ref "R89") (pin "2") (pinfunction "2_2") (pintype "passive"))
    )
    (net (code "76") (name "Net-(IC11A-OUT)") (class "Default")
      (node (ref "C40") (pin "1") (pinfunction "1_1") (pintype "passive"))
      (node (ref "IC11") (pin "4") (pinfunction "OUT_4") (pintype "output"))
      (node (ref "IC9") (pin "6") (pinfunction "-IN_6") (pintype "input"))
    )
    (net (code "77") (name "Net-(IC11B-IN)") (class "Default")
      (node (ref "IC11") (pin "7") (pinfunction "IN_7") (pintype "input"))
      (node (ref "R94") (pin "2") (pinfunction "2_2") (pintype "passive"))
      (node (ref "R98") (pin "2") (pinfunction "2_2") (pintype "passive"))
    )
    (net (code "78") (name "Net-(IC11B-OUT)") (class "Default")
      (node (ref "IC11") (pin "5") (pinfunction "OUT_5") (pintype "output"))
      (node (ref "IC9") (pin "13") (pinfunction "-IN_13") (pintype "input"))
      (node (ref "R76") (pin "2") (pinfunction "2_2") (pintype "passive"))
    )
    (net (code "79") (name "Net-(IC11C-IN)") (class "Default")
      (node (ref "IC11") (pin "10") (pinfunction "IN_10") (pintype "input"))
      (node (ref "R97") (pin "2") (pinfunction "2_2") (pintype "passive"))
      (node (ref "R99") (pin "2") (pinfunction "2_2") (pintype "passive"))
    )
    (net (code "80") (name "Net-(IC11D-IN)") (class "Default")
      (node (ref "IC11") (pin "15") (pinfunction "IN_15") (pintype "input"))
      (node (ref "R87") (pin "2") (pinfunction "2_2") (pintype "passive"))
      (node (ref "R90") (pin "2") (pinfunction "2_2") (pintype "passive"))
    )
    (net (code "81") (name "Net-(IC11D-OUT)") (class "Default")
      (node (ref "C41") (pin "1") (pinfunction "1_1") (pintype "passive"))
      (node (ref "IC11") (pin "13") (pinfunction "OUT_13") (pintype "output"))
      (node (ref "IC9") (pin "9") (pinfunction "-IN_9") (pintype "input"))
    )
    (net (code "82") (name "Net-(IC12A--IN)") (class "Default")
      (node (ref "IC12") (pin "2") (pinfunction "-IN_2") (pintype "input"))
      (node (ref "R102") (pin "1") (pinfunction "1_1") (pintype "passive"))
      (node (ref "R105") (pin "2") (pinfunction "2_2") (pintype "passive"))
    )
    (net (code "83") (name "Net-(IC12A-OUT)") (class "Default")
      (node (ref "IC12") (pin "1") (pinfunction "OUT_1") (pintype "output"))
      (node (ref "R102") (pin "2") (pinfunction "2_2") (pintype "passive"))
      (node (ref "R106") (pin "1") (pinfunction "1_1") (pintype "passive"))
    )
    (net (code "84") (name "Net-(IC12B--IN)") (class "Default")
      (node (ref "IC12") (pin "6") (pinfunction "-IN_6") (pintype "input"))
      (node (ref "R103") (pin "1") (pinfunction "1_1") (pintype "passive"))
      (node (ref "R106") (pin "2") (pinfunction "2_2") (pintype "passive"))
      (node (ref "R122") (pin "1") (pinfunction "1_1") (pintype "passive"))
    )
    (net (code "85") (name "Net-(IC13B-OUT)") (class "Default")
      (node (ref "IC13") (pin "7") (pinfunction "OUT_7") (pintype "output"))
      (node (ref "R104") (pin "1") (pinfunction "1_1") (pintype "passive"))
      (node (ref "R110") (pin "2") (pinfunction "2_2") (pintype "passive"))
    )
    (net (code "86") (name "Net-(IC14A-+IN)") (class "Default")
      (node (ref "IC14") (pin "3") (pinfunction "+IN_3") (pintype "input"))
      (node (ref "IC14") (pin "6") (pinfunction "-IN_6") (pintype "input"))
      (node (ref "R115") (pin "2") (pinfunction "2_2") (pintype "passive"))
      (node (ref "R117") (pin "2") (pinfunction "2_2") (pintype "passive"))
      (node (ref "R118") (pin "1") (pinfunction "1_1") (pintype "passive"))
    )
    (net (code "87") (name "Net-(IC14A--IN)") (class "Default")
      (node (ref "IC14") (pin "2") (pinfunction "-IN_2") (pintype "input"))
      (node (ref "R119") (pin "2") (pinfunction "2_2") (pintype "passive"))
      (node (ref "R121") (pin "1") (pinfunction "1_1") (pintype "passive"))
    )
    (net (code "88") (name "Net-(IC14A-OUT)") (class "Default")
      (node (ref "D13") (pin "A") (pinfunction "A_A") (pintype "passive"))
      (node (ref "IC14") (pin "1") (pinfunction "OUT_1") (pintype "output"))
    )
    (net (code "89") (name "Net-(IC14B-+IN)") (class "Default")
      (node (ref "IC14") (pin "5") (pinfunction "+IN_5") (pintype "input"))
      (node (ref "R119") (pin "1") (pinfunction "1_1") (pintype "passive"))
      (node (ref "R120") (pin "2") (pinfunction "2_2") (pintype "passive"))
    )
    (net (code "90") (name "Net-(IC14B-OUT)") (class "Default")
      (node (ref "D14") (pin "A") (pinfunction "A_A") (pintype "passive"))
      (node (ref "IC14") (pin "7") (pinfunction "OUT_7") (pintype "output"))
    )
    (net (code "91") (name "Net-(J1-3)") (class "Default")
      (node (ref "J1") (pin "P3") (pinfunction "3_P3") (pintype "passive"))
      (node (ref "R6") (pin "1") (pinfunction "1_1") (pintype "passive"))
    )
    (net (code "92") (name "Net-(J2-3)") (class "Default")
      (node (ref "J2") (pin "P3") (pinfunction "3_P3") (pintype "passive"))
      (node (ref "R30") (pin "1") (pinfunction "1_1") (pintype "passive"))
    )
    (net (code "93") (name "Net-(J3-3)") (class "Default")
      (node (ref "J3") (pin "P3") (pinfunction "3_P3") (pintype "passive"))
      (node (ref "R48") (pin "1") (pinfunction "1_1") (pintype "passive"))
    )
    (net (code "94") (name "Net-(J4-3)") (class "Default")
      (node (ref "J4") (pin "P3") (pinfunction "3_P3") (pintype "passive"))
      (node (ref "R45") (pin "1") (pinfunction "1_1") (pintype "passive"))
    )
    (net (code "95") (name "Net-(J5-3)") (class "Default")
      (node (ref "J5") (pin "P3") (pinfunction "3_P3") (pintype "passive"))
      (node (ref "R58") (pin "1") (pinfunction "1_1") (pintype "passive"))
    )
    (net (code "96") (name "Net-(J6-3)") (class "Default")
      (node (ref "J6") (pin "P3") (pinfunction "3_P3") (pintype "passive"))
      (node (ref "R91") (pin "1") (pinfunction "1_1") (pintype "passive"))
    )
    (net (code "97") (name "Net-(J7-3)") (class "Default")
      (node (ref "J7") (pin "P3") (pinfunction "3_P3") (pintype "passive"))
      (node (ref "R82") (pin "1") (pinfunction "1_1") (pintype "passive"))
    )
    (net (code "98") (name "Net-(J8-3)") (class "Default")
      (node (ref "J8") (pin "P3") (pinfunction "3_P3") (pintype "passive"))
      (node (ref "R78") (pin "1") (pinfunction "1_1") (pintype "passive"))
    )
    (net (code "99") (name "Net-(J9-3)") (class "Default")
      (node (ref "J9") (pin "P3") (pinfunction "3_P3") (pintype "passive"))
      (node (ref "R9") (pin "1") (pinfunction "1_1") (pintype "passive"))
    )
    (net (code "100") (name "Net-(J10-3)") (class "Default")
      (node (ref "J10") (pin "P3") (pinfunction "3_P3") (pintype "passive"))
      (node (ref "R27") (pin "1") (pinfunction "1_1") (pintype "passive"))
    )
    (net (code "101") (name "Net-(J13-3)") (class "Default")
      (node (ref "J13") (pin "P3") (pinfunction "3_P3") (pintype "passive"))
      (node (ref "R105") (pin "1") (pinfunction "1_1") (pintype "passive"))
    )
    (net (code "102") (name "Net-(J14-3)") (class "Default")
      (node (ref "J14") (pin "P3") (pinfunction "3_P3") (pintype "passive"))
      (node (ref "R111") (pin "2") (pinfunction "2_2") (pintype "passive"))
    )
    (net (code "103") (name "Net-(JP11-Pad10)") (class "Default")
      (node (ref "JP11") (pin "10") (pinfunction "10_10") (pintype "passive"))
      (node (ref "JP11") (pin "9") (pinfunction "9_9") (pintype "passive"))
      (node (ref "P1") (pin "2") (pinfunction "2_2") (pintype "bidirectional"))
    )
    (net (code "104") (name "Net-(JP12-Pad2)") (class "Default")
      (node (ref "JP12") (pin "2") (pinfunction "2_2") (pintype "passive"))
      (node (ref "R122") (pin "2") (pinfunction "2_2") (pintype "passive"))
    )
    (net (code "105") (name "Net-(LED1-C)") (class "Default")
      (node (ref "LED1") (pin "K") (pinfunction "C_K") (pintype "passive"))
      (node (ref "Q1") (pin "C") (pinfunction "C_C") (pintype "passive"))
    )
    (net (code "106") (name "Net-(LED1-PadA)") (class "Default")
      (node (ref "LED1") (pin "A") (pinfunction "A_A") (pintype "passive"))
      (node (ref "R112") (pin "1") (pinfunction "1_1") (pintype "passive"))
    )
    (net (code "107") (name "Net-(Q1-PadB)") (class "Default")
      (node (ref "Q1") (pin "B") (pinfunction "B_B") (pintype "passive"))
      (node (ref "R114") (pin "2") (pinfunction "2_2") (pintype "passive"))
      (node (ref "R116") (pin "2") (pinfunction "2_2") (pintype "passive"))
    )
    (net (code "108") (name "Net-(R3-S)") (class "Default")
      (node (ref "R3") (pin "P$2") (pinfunction "S_P$2") (pintype "passive"))
      (node (ref "R5") (pin "2") (pinfunction "2_2") (pintype "passive"))
    )
    (net (code "109") (name "Net-(R4-S)") (class "Default")
      (node (ref "R12") (pin "2") (pinfunction "2_2") (pintype "passive"))
      (node (ref "R4") (pin "P$2") (pinfunction "S_P$2") (pintype "passive"))
    )
    (net (code "110") (name "Net-(R34-S)") (class "Default")
      (node (ref "R34") (pin "P$2") (pinfunction "S_P$2") (pintype "passive"))
      (node (ref "R43") (pin "2") (pinfunction "2_2") (pintype "passive"))
    )
    (net (code "111") (name "Net-(R36-S)") (class "Default")
      (node (ref "R36") (pin "P$2") (pinfunction "S_P$2") (pintype "passive"))
      (node (ref "R49") (pin "2") (pinfunction "2_2") (pintype "passive"))
    )
    (net (code "112") (name "Net-(R39-Pad2)") (class "Default")
      (node (ref "R39") (pin "2") (pinfunction "2_2") (pintype "passive"))
      (node (ref "R41") (pin "1") (pinfunction "1_1") (pintype "passive"))
    )
    (net (code "113") (name "Net-(R42-S)") (class "Default")
      (node (ref "R42") (pin "P$2") (pinfunction "S_P$2") (pintype "passive"))
      (node (ref "R54") (pin "2") (pinfunction "2_2") (pintype "passive"))
    )
    (net (code "114") (name "Net-(R65-S)") (class "Default")
      (node (ref "R65") (pin "P$2") (pinfunction "S_P$2") (pintype "passive"))
      (node (ref "R70") (pin "2") (pinfunction "2_2") (pintype "passive"))
    )
    (net (code "115") (name "Net-(R68-S)") (class "Default")
      (node (ref "R68") (pin "P$2") (pinfunction "S_P$2") (pintype "passive"))
      (node (ref "R77") (pin "2") (pinfunction "2_2") (pintype "passive"))
    )
    (net (code "116") (name "Net-(R69-S)") (class "Default")
      (node (ref "R69") (pin "P$2") (pinfunction "S_P$2") (pintype "passive"))
      (node (ref "R83") (pin "2") (pinfunction "2_2") (pintype "passive"))
    )
    (net (code "117") (name "Net-(R74-Pad2)") (class "Default")
      (node (ref "R74") (pin "2") (pinfunction "2_2") (pintype "passive"))
      (node (ref "R76") (pin "1") (pinfunction "1_1") (pintype "passive"))
    )
    (net (code "118") (name "Net-(R100-S)") (class "Default")
      (node (ref "R100") (pin "P$2") (pinfunction "S_P$2") (pintype "passive"))
      (node (ref "R109") (pin "2") (pinfunction "2_2") (pintype "passive"))
    )
    (net (code "119") (name "Net-(R101-S)") (class "Default")
      (node (ref "R101") (pin "P$2") (pinfunction "S_P$2") (pintype "passive"))
      (node (ref "R108") (pin "2") (pinfunction "2_2") (pintype "passive"))
    )
    (net (code "120") (name "OUTPUT") (class "Default")
      (node (ref "C57") (pin "2") (pinfunction "2_2") (pintype "passive"))
      (node (ref "IC13") (pin "1") (pinfunction "OUT_1") (pintype "output"))
      (node (ref "R107") (pin "2") (pinfunction "2_2") (pintype "passive"))
      (node (ref "R111") (pin "1") (pinfunction "1_1") (pintype "passive"))
    )
    (net (code "121") (name "PLUS_BUS") (class "Default")
      (node (ref "IC13") (pin "6") (pinfunction "-IN_6") (pintype "input"))
      (node (ref "IC5") (pin "12") (pinfunction "OUT_12") (pintype "output"))
      (node (ref "R110") (pin "1") (pinfunction "1_1") (pintype "passive"))
      (node (ref "R33") (pin "2") (pinfunction "2_2") (pintype "passive"))
      (node (ref "R55") (pin "2") (pinfunction "2_2") (pintype "passive"))
      (node (ref "R88") (pin "2") (pinfunction "2_2") (pintype "passive"))
    )
    (net (code "122") (name "VCC") (class "Default")
      (node (ref "C1") (pin "+") (pinfunction "+_+") (pintype "passive"))
      (node (ref "C12") (pin "1") (pinfunction "1_1") (pintype "passive"))
      (node (ref "C21") (pin "1") (pinfunction "1_1") (pintype "passive"))
      (node (ref "C27") (pin "1") (pinfunction "1_1") (pintype "passive"))
      (node (ref "C31") (pin "1") (pinfunction "1_1") (pintype "passive"))
      (node (ref "C36") (pin "1") (pinfunction "1_1") (pintype "passive"))
      (node (ref "C42") (pin "1") (pinfunction "1_1") (pintype "passive"))
      (node (ref "C43") (pin "1") (pinfunction "1_1") (pintype "passive"))
      (node (ref "C5") (pin "1") (pinfunction "1_1") (pintype "passive"))
      (node (ref "C50") (pin "1") (pinfunction "1_1") (pintype "passive"))
      (node (ref "C52") (pin "1") (pinfunction "1_1") (pintype "passive"))
      (node (ref "C56") (pin "1") (pinfunction "1_1") (pintype "passive"))
      (node (ref "C58") (pin "+") (pinfunction "+_+") (pintype "passive"))
      (node (ref "C9") (pin "1") (pinfunction "1_1") (pintype "passive"))
      (node (ref "D2") (pin "C") (pinfunction "C_C") (pintype "passive"))
      (node (ref "IC10") (pin "4") (pinfunction "V+_4") (pintype "power_in"))
      (node (ref "IC11") (pin "16") (pinfunction "V+_16") (pintype "power_in"))
      (node (ref "IC12") (pin "8") (pinfunction "V+_8") (pintype "power_in"))
      (node (ref "IC13") (pin "8") (pinfunction "V+_8") (pintype "power_in"))
      (node (ref "IC14") (pin "8") (pinfunction "V+_8") (pintype "power_in"))
      (node (ref "IC3") (pin "8") (pinfunction "V+_8") (pintype "power_in"))
      (node (ref "IC4") (pin "4") (pinfunction "V+_4") (pintype "power_in"))
      (node (ref "IC5") (pin "16") (pinfunction "V+_16") (pintype "power_in"))
      (node (ref "IC6") (pin "4") (pinfunction "V+_4") (pintype "power_in"))
      (node (ref "IC7") (pin "4") (pinfunction "V+_4") (pintype "power_in"))
      (node (ref "IC8") (pin "16") (pinfunction "V+_16") (pintype "power_in"))
      (node (ref "IC9") (pin "4") (pinfunction "V+_4") (pintype "power_in"))
      (node (ref "R1") (pin "1") (pinfunction "1_1") (pintype "passive"))
      (node (ref "R112") (pin "2") (pinfunction "2_2") (pintype "passive"))
    )
    (net (code "123") (name "VEE") (class "Default")
      (node (ref "C13") (pin "2") (pinfunction "2_2") (pintype "passive"))
      (node (ref "C2") (pin "-") (pinfunction "-_-") (pintype "passive"))
      (node (ref "C20") (pin "2") (pinfunction "2_2") (pintype "passive"))
      (node (ref "C22") (pin "2") (pinfunction "2_2") (pintype "passive"))
      (node (ref "C28") (pin "2") (pinfunction "2_2") (pintype "passive"))
      (node (ref "C35") (pin "2") (pinfunction "2_2") (pintype "passive"))
      (node (ref "C37") (pin "2") (pinfunction "2_2") (pintype "passive"))
      (node (ref "C44") (pin "2") (pinfunction "2_2") (pintype "passive"))
      (node (ref "C51") (pin "2") (pinfunction "2_2") (pintype "passive"))
      (node (ref "C53") (pin "2") (pinfunction "2_2") (pintype "passive"))
      (node (ref "C54") (pin "2") (pinfunction "2_2") (pintype "passive"))
      (node (ref "C8") (pin "2") (pinfunction "2_2") (pintype "passive"))
      (node (ref "D1") (pin "A") (pinfunction "A_A") (pintype "passive"))
      (node (ref "IC10") (pin "11") (pinfunction "V-_11") (pintype "power_in"))
      (node (ref "IC11") (pin "9") (pinfunction "V-_9") (pintype "power_in"))
      (node (ref "IC12") (pin "4") (pinfunction "V-_4") (pintype "power_in"))
      (node (ref "IC13") (pin "4") (pinfunction "V-_4") (pintype "power_in"))
      (node (ref "IC3") (pin "4") (pinfunction "V-_4") (pintype "power_in"))
      (node (ref "IC4") (pin "11") (pinfunction "V-_11") (pintype "power_in"))
      (node (ref "IC5") (pin "9") (pinfunction "V-_9") (pintype "power_in"))
      (node (ref "IC6") (pin "11") (pinfunction "V-_11") (pintype "power_in"))
      (node (ref "IC7") (pin "11") (pinfunction "V-_11") (pintype "power_in"))
      (node (ref "IC8") (pin "9") (pinfunction "V-_9") (pintype "power_in"))
      (node (ref "IC9") (pin "11") (pinfunction "V-_11") (pintype "power_in"))
      (node (ref "P1") (pin "1") (pinfunction "1_1") (pintype "bidirectional"))
      (node (ref "R2") (pin "1") (pinfunction "1_1") (pintype "passive"))
    )
    (net (code "124") (name "unconnected-(IC5E-MODE-Pad1)") (class "Default")
      (node (ref "IC5") (pin "1") (pinfunction "MODE_1") (pintype "input"))
    )
    (net (code "125") (name "unconnected-(IC8E-MODE-Pad1)") (class "Default")
      (node (ref "IC8") (pin "1") (pinfunction "MODE_1") (pintype "input"))
    )
    (net (code "126") (name "unconnected-(IC11E-MODE-Pad1)") (class "Default")
      (node (ref "IC11") (pin "1") (pinfunction "MODE_1") (pintype "input"))
    )
    (net (code "127") (name "unconnected-(J1-2-PadP2)") (class "Default")
      (node (ref "J1") (pin "P2") (pinfunction "2_P2") (pintype "passive"))
    )
    (net (code "128") (name "unconnected-(J2-2-PadP2)") (class "Default")
      (node (ref "J2") (pin "P2") (pinfunction "2_P2") (pintype "passive"))
    )
    (net (code "129") (name "unconnected-(J3-2-PadP2)") (class "Default")
      (node (ref "J3") (pin "P2") (pinfunction "2_P2") (pintype "passive"))
    )
    (net (code "130") (name "unconnected-(J4-2-PadP2)") (class "Default")
      (node (ref "J4") (pin "P2") (pinfunction "2_P2") (pintype "passive"))
    )
    (net (code "131") (name "unconnected-(J5-2-PadP2)") (class "Default")
      (node (ref "J5") (pin "P2") (pinfunction "2_P2") (pintype "passive"))
    )
    (net (code "132") (name "unconnected-(J6-2-PadP2)") (class "Default")
      (node (ref "J6") (pin "P2") (pinfunction "2_P2") (pintype "passive"))
    )
    (net (code "133") (name "unconnected-(J7-2-PadP2)") (class "Default")
      (node (ref "J7") (pin "P2") (pinfunction "2_P2") (pintype "passive"))
    )
    (net (code "134") (name "unconnected-(J8-2-PadP2)") (class "Default")
      (node (ref "J8") (pin "P2") (pinfunction "2_P2") (pintype "passive"))
    )
    (net (code "135") (name "unconnected-(J9-2-PadP2)") (class "Default")
      (node (ref "J9") (pin "P2") (pinfunction "2_P2") (pintype "passive"))
    )
    (net (code "136") (name "unconnected-(J10-2-PadP2)") (class "Default")
      (node (ref "J10") (pin "P2") (pinfunction "2_P2") (pintype "passive"))
    )
    (net (code "137") (name "unconnected-(J11-2-PadP2)") (class "Default")
      (node (ref "J11") (pin "P2") (pinfunction "2_P2") (pintype "passive"))
    )
    (net (code "138") (name "unconnected-(J12-2-PadP2)") (class "Default")
      (node (ref "J12") (pin "P2") (pinfunction "2_P2") (pintype "passive"))
    )
    (net (code "139") (name "unconnected-(J13-2-PadP2)") (class "Default")
      (node (ref "J13") (pin "P2") (pinfunction "2_P2") (pintype "passive"))
    )
    (net (code "140") (name "unconnected-(J14-2-PadP2)") (class "Default")
      (node (ref "J14") (pin "P2") (pinfunction "2_P2") (pintype "passive"))
    )
    (net (code "141") (name "unconnected-(JP12-Pad1)") (class "Default")
      (node (ref "JP12") (pin "1") (pinfunction "1_1") (pintype "passive"))
    )
  )
)
